# AT32M412_EVB_V0_3.net
KiCad netlist of a schematic drawn in EasyEDA Pro
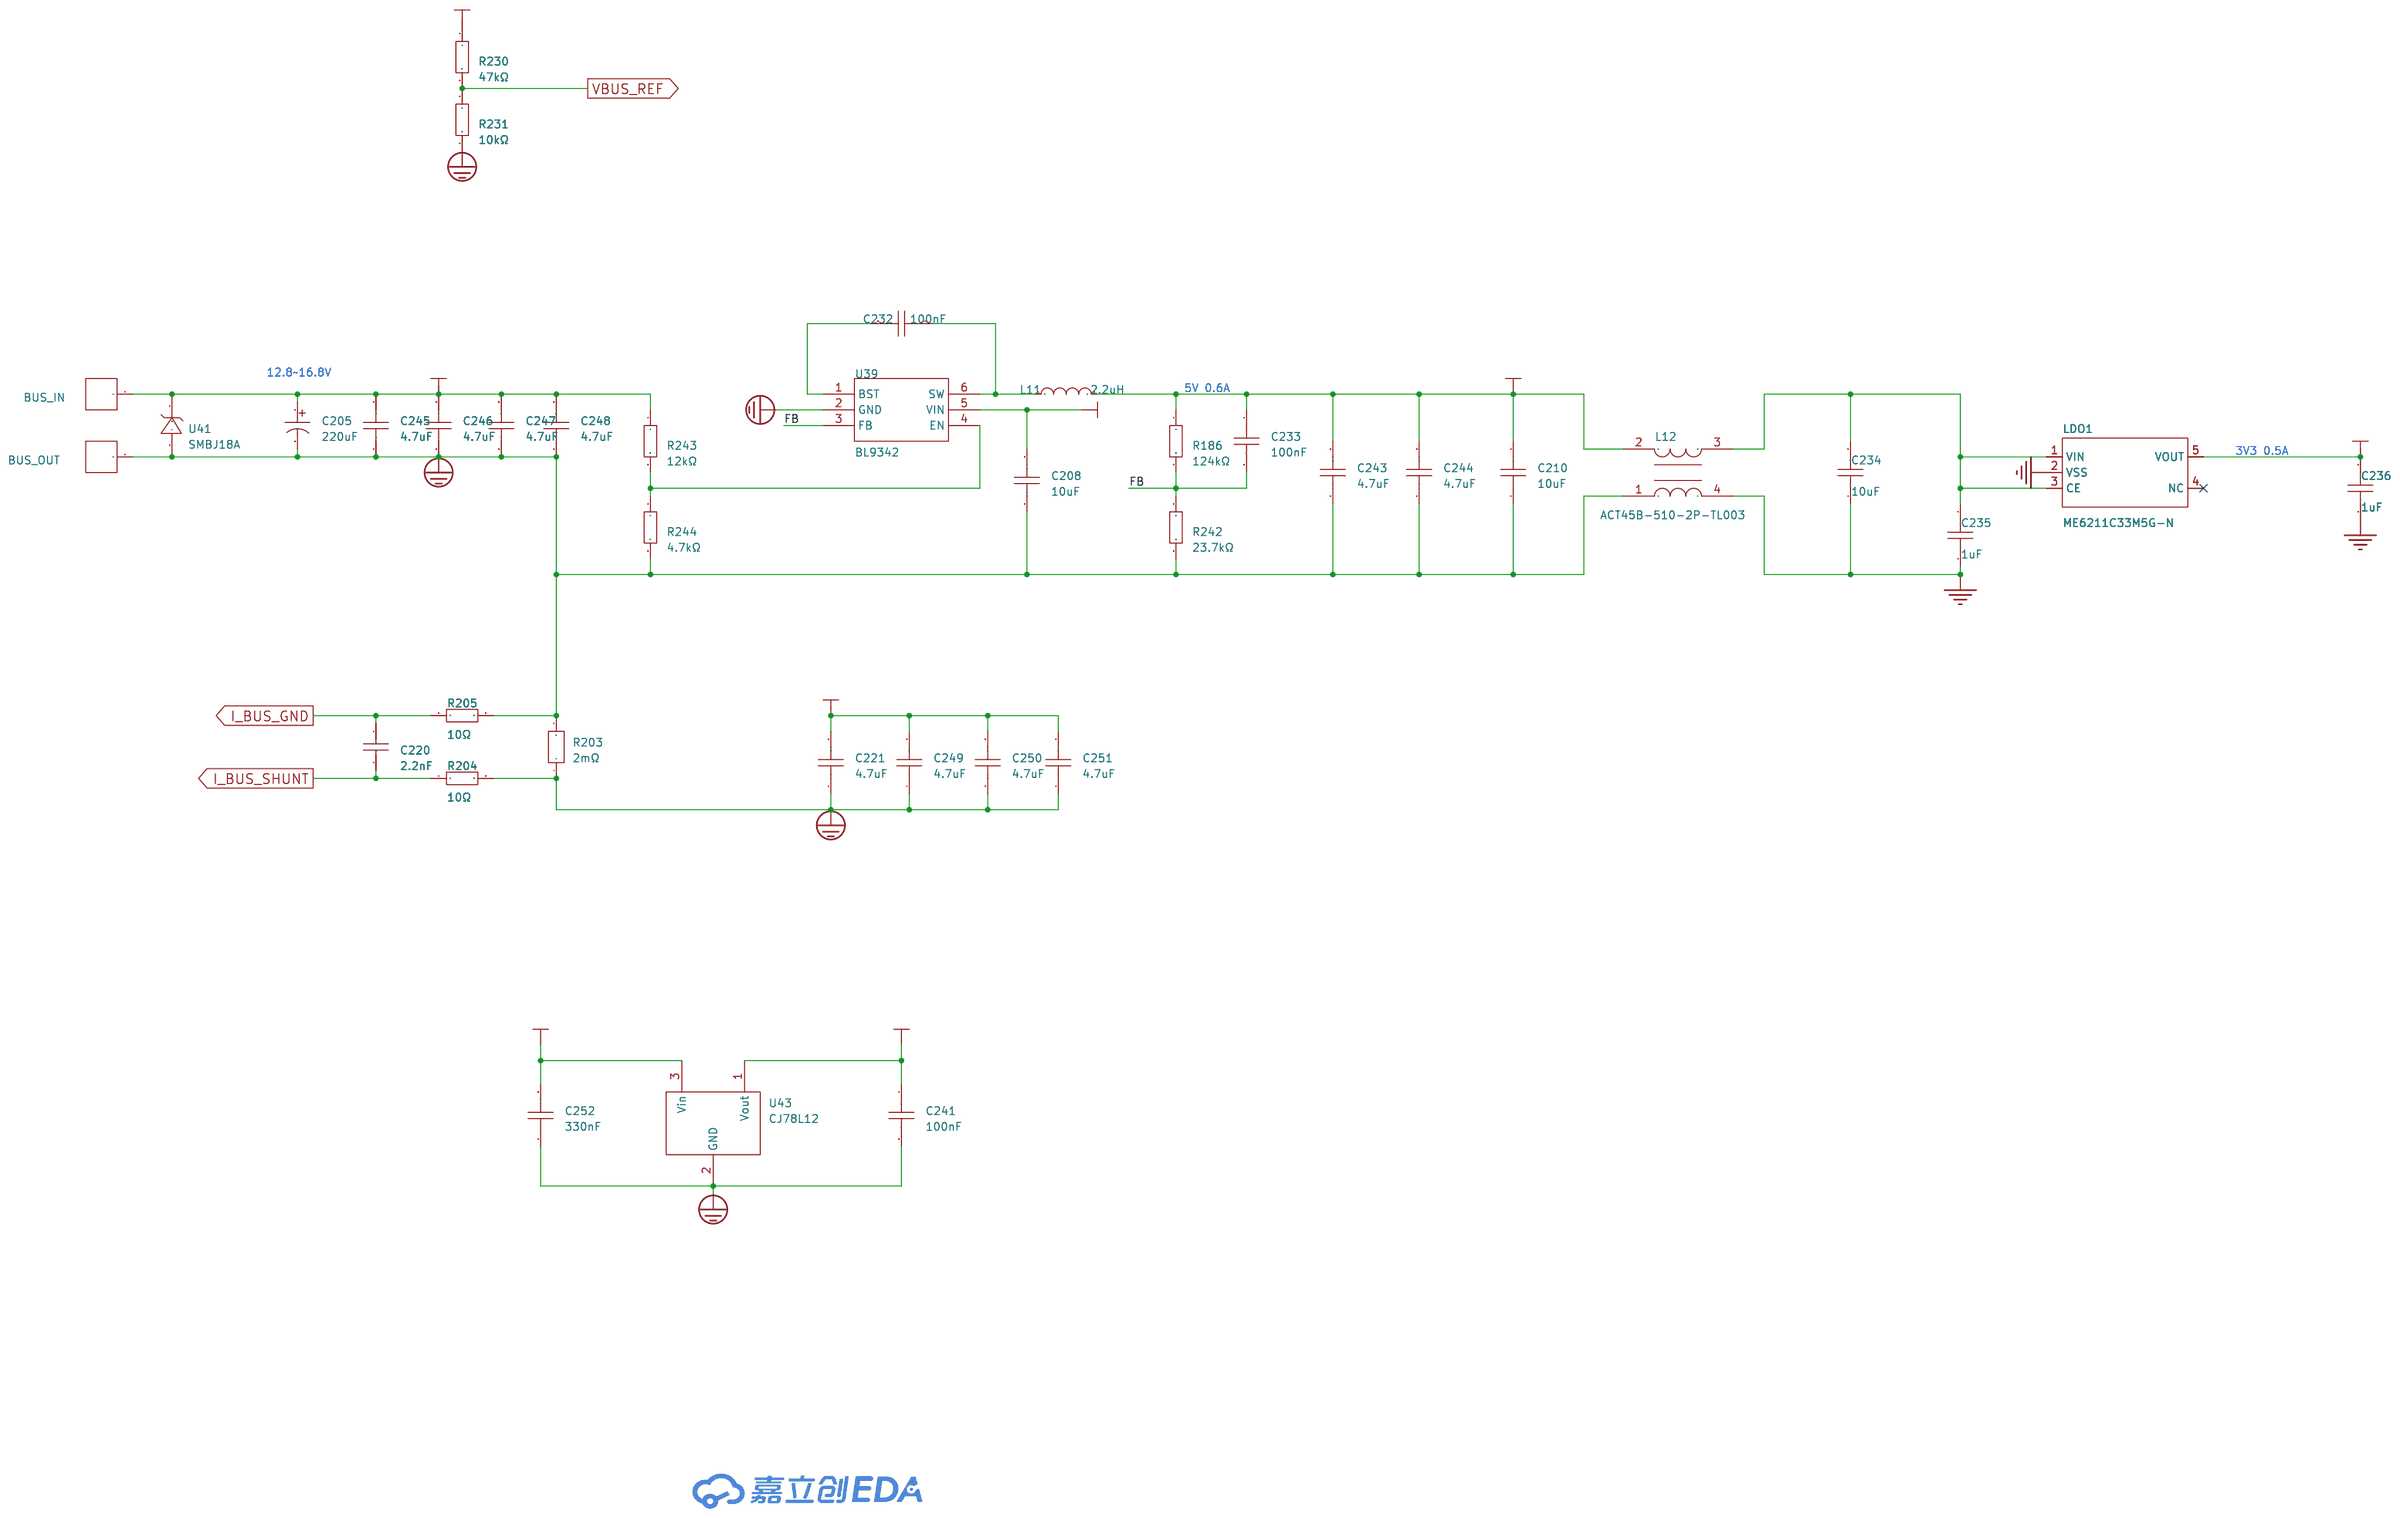
[diagram p0: PWR]
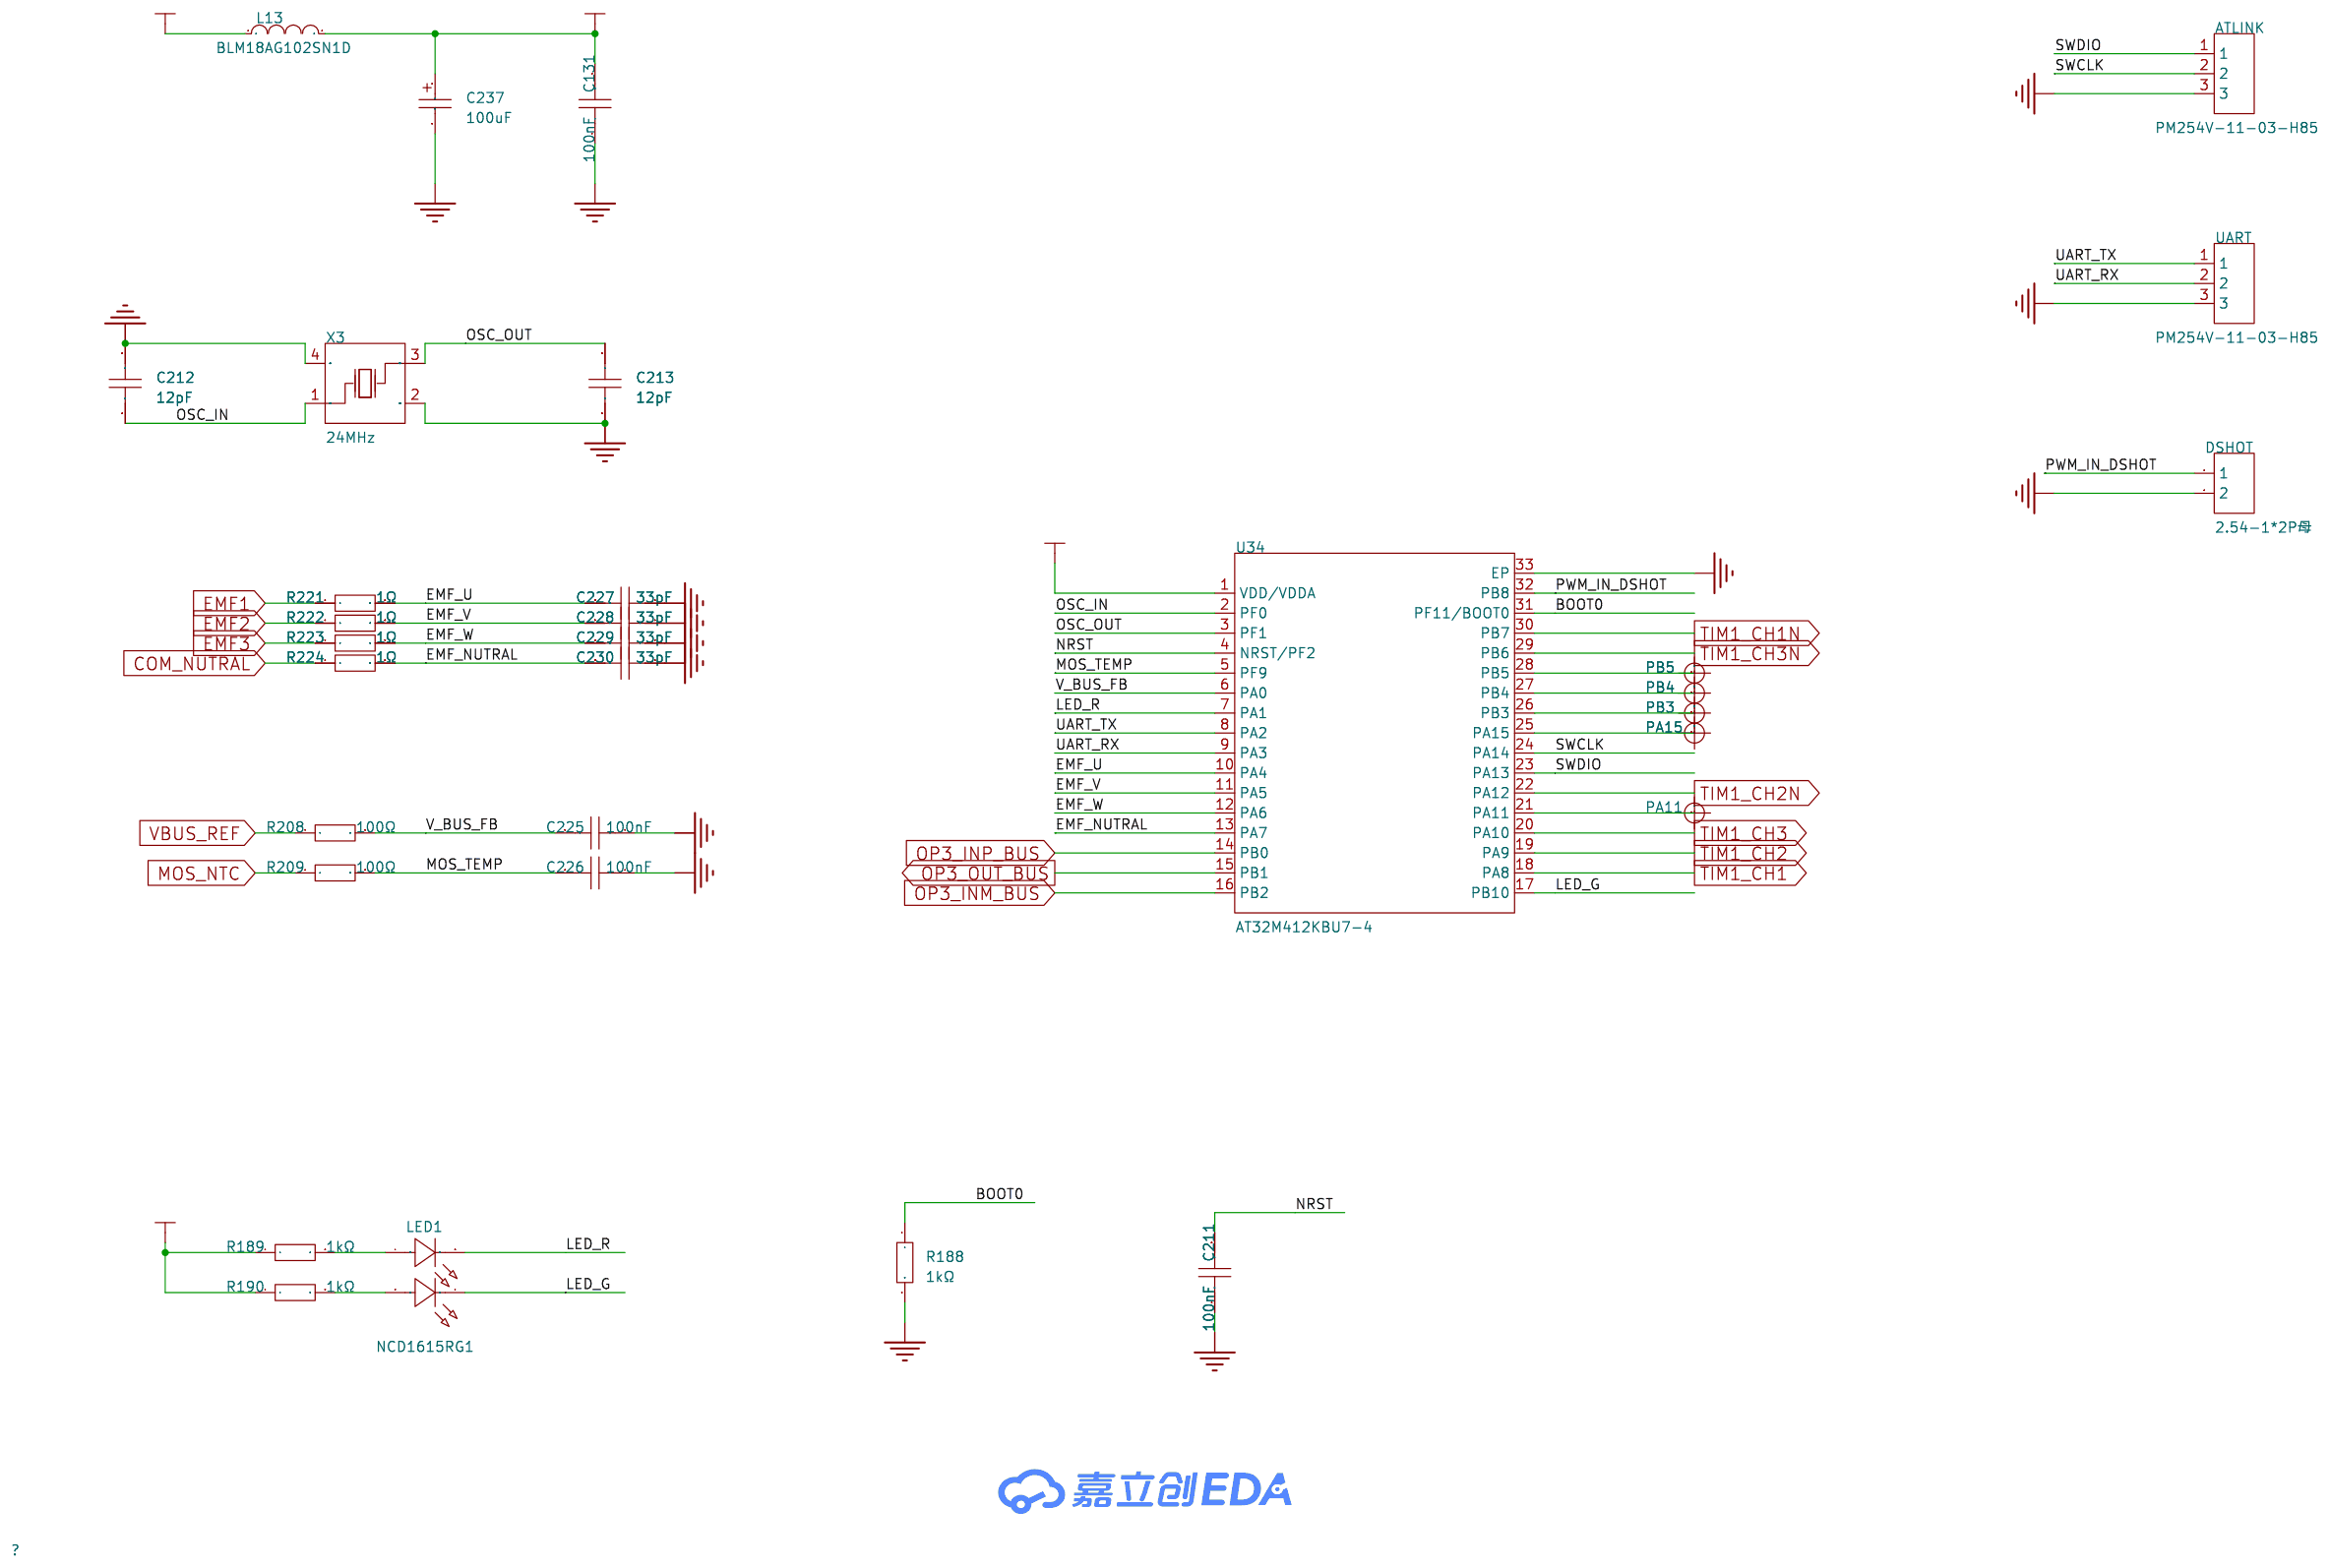
[diagram p1: MCU]
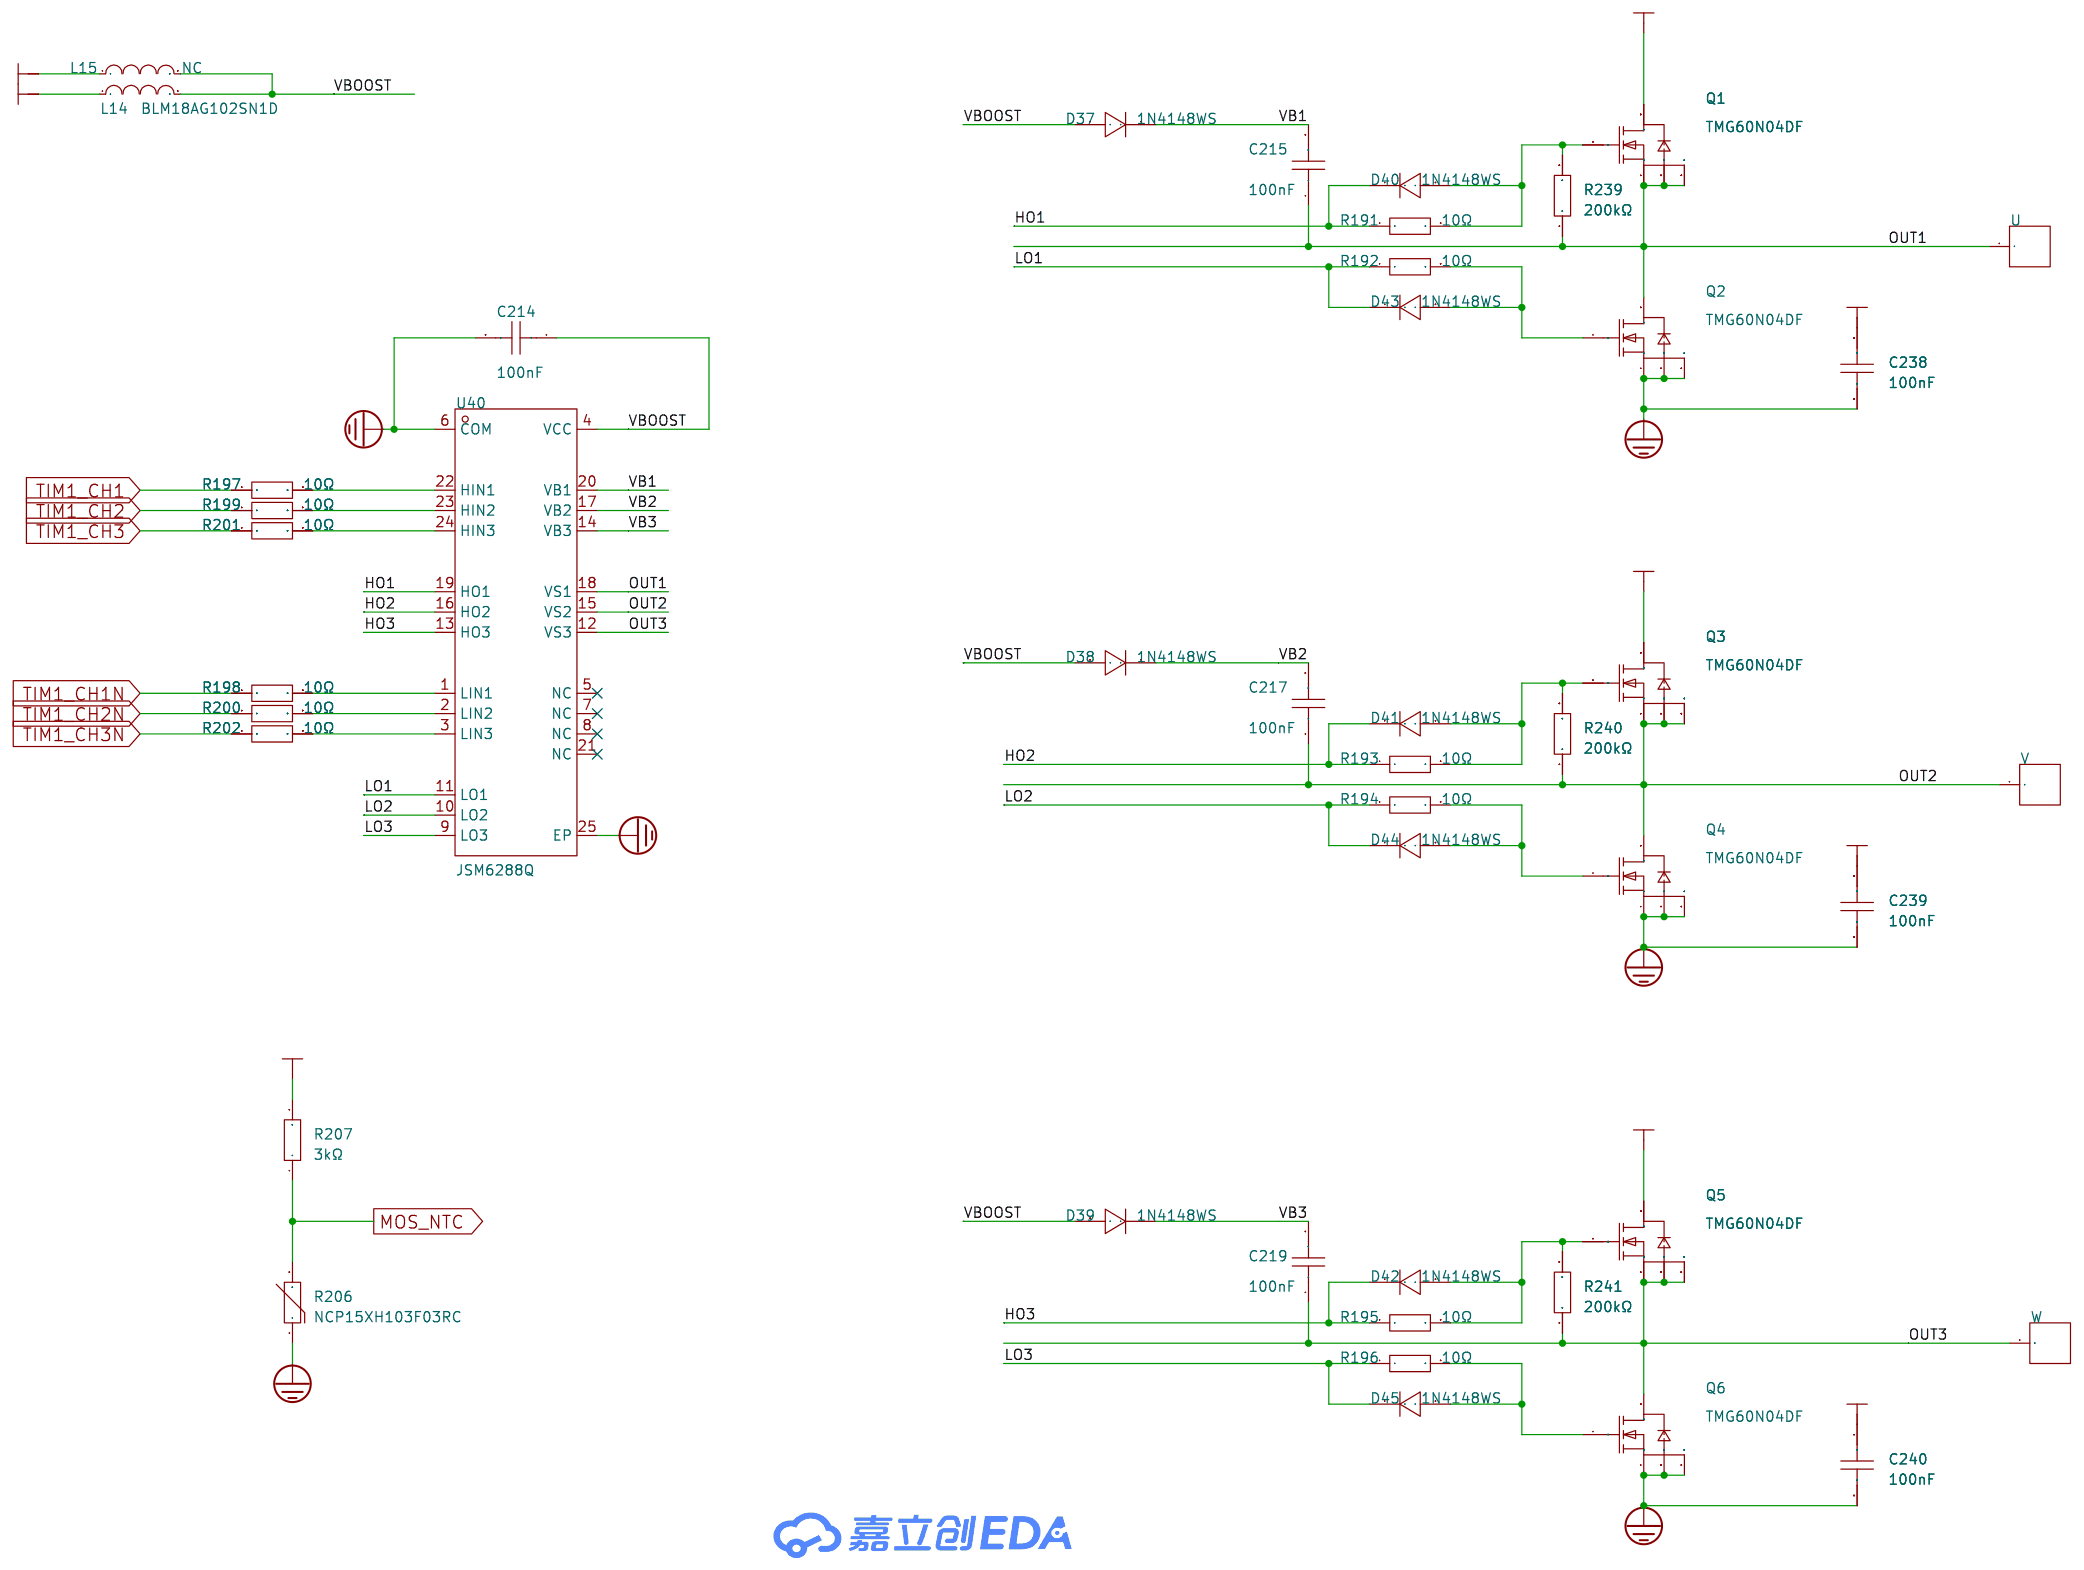
[diagram p2: Driver]
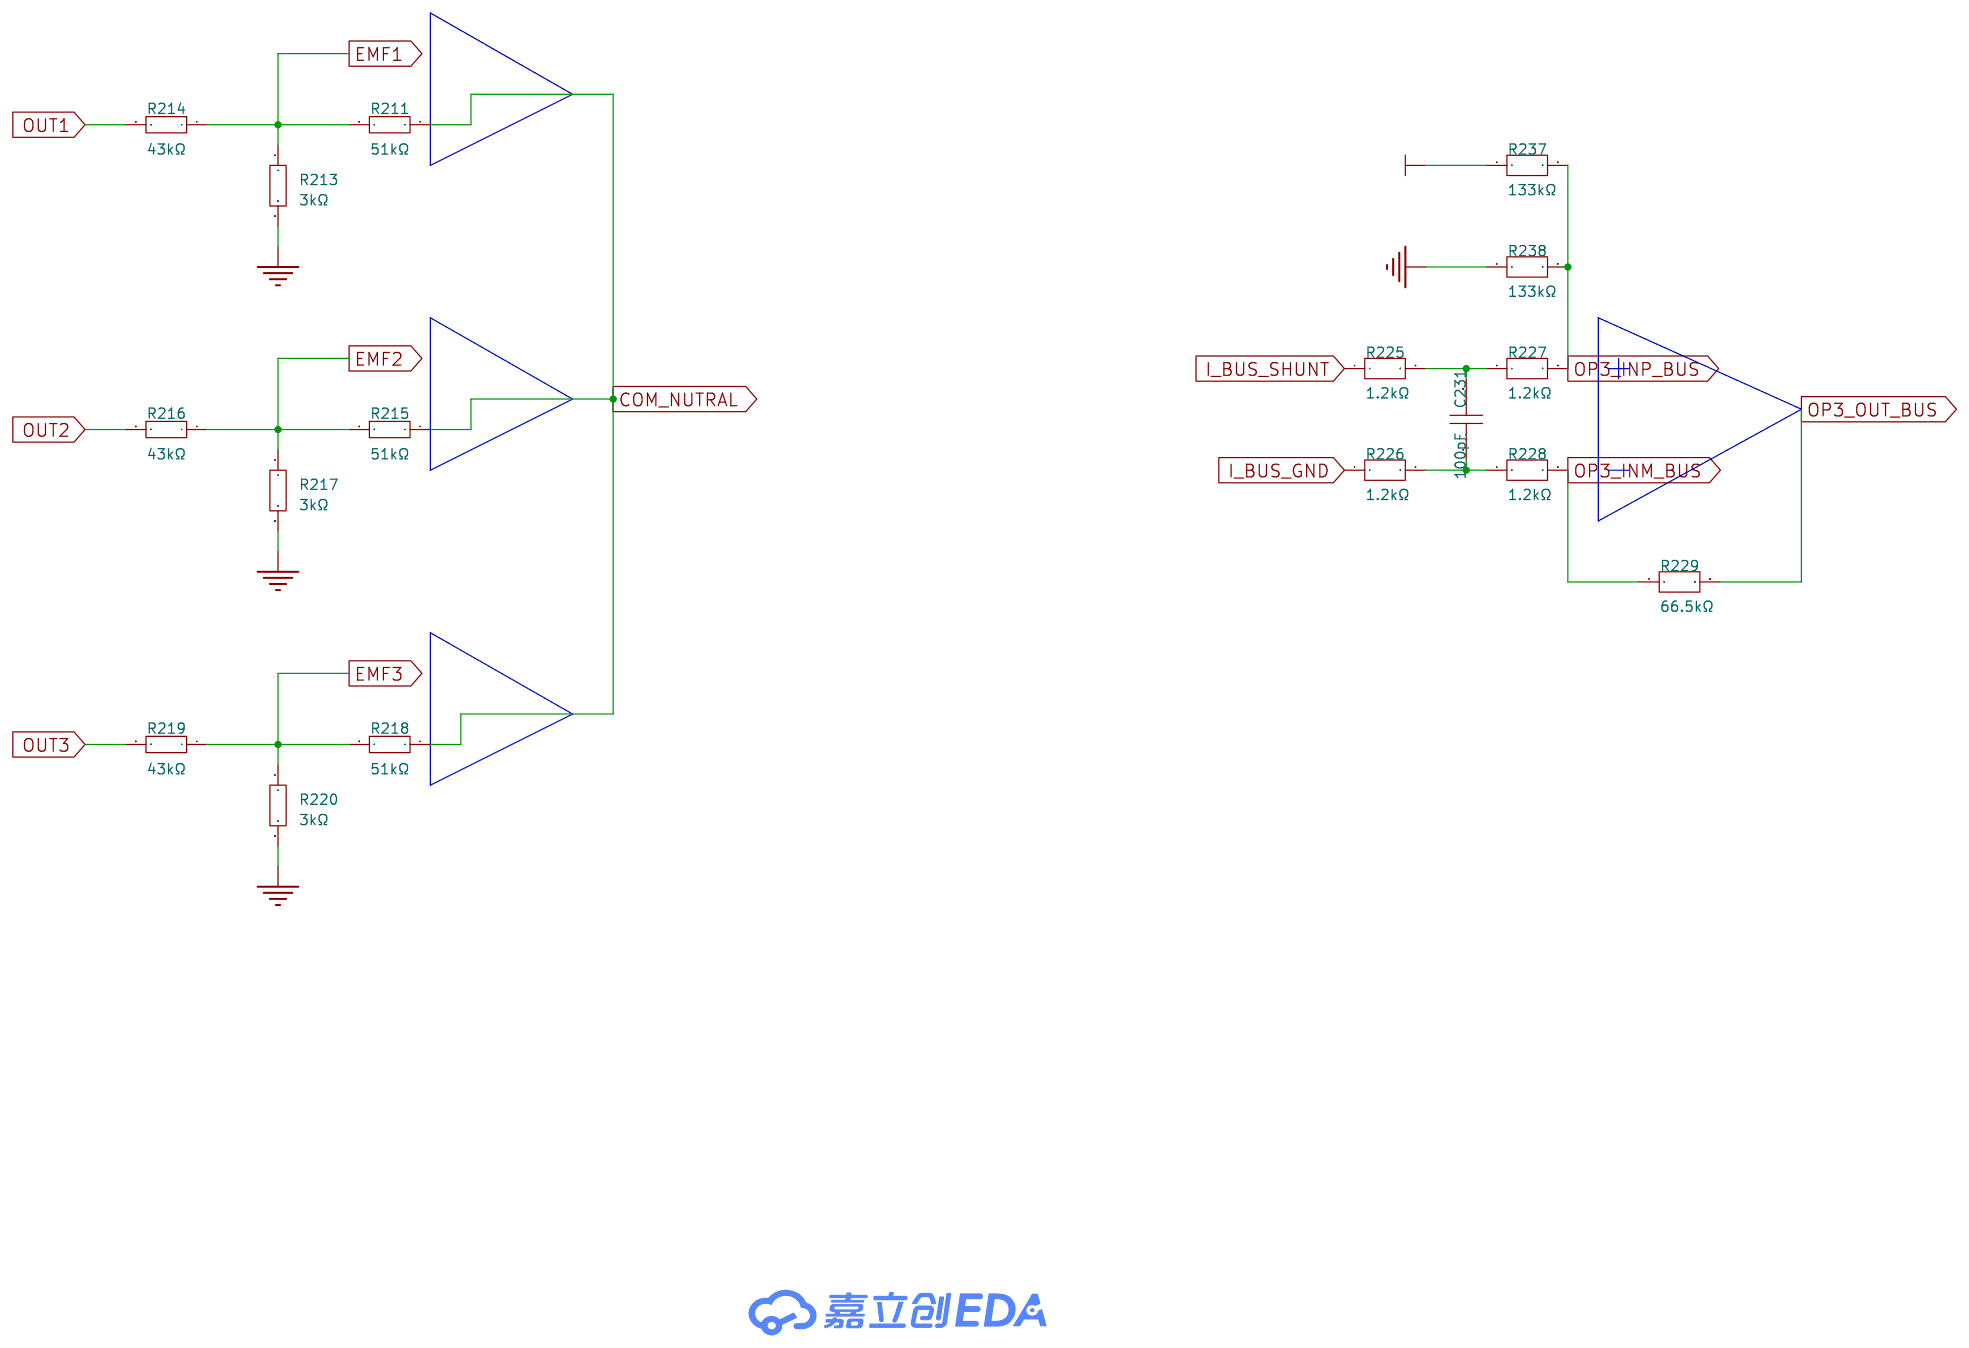
[diagram p3: Sensing]

(export (version "E")
  (design (tool "Eeschema 10.0.6"))
  (components
    (comp (ref "BUS_IN")
      (value "~")
      (footprint "easyedapro:PAD_35A")
      (description "焊盘")
      (libsource (lib "easyedapro") (part "PAD_35A"))
    )
    (comp (ref "BUS_OUT")
      (value "~")
      (footprint "easyedapro:PAD_35A")
      (description "焊盘")
      (libsource (lib "easyedapro") (part "PAD_35A"))
    )
    (comp (ref "C205")
      (value "220uF")
      (footprint "easyedapro:CAP-TH_BD8.0-P3.50-D0.6-FD")
      (description "容值:220uF;精度:±20%;额定电压:35V;")
      (fields (field (name "Manufacturer Part") "ERS1VM221F12OT") (field (name "Manufacturer") "AISHI(艾华集团)"))
      (libsource (lib "easyedapro") (part "ERS1VM221F12OT"))
    )
    (comp (ref "C208")
      (value "10uF")
      (footprint "easyedapro:C0805")
      (description "容值:10uF;精度:±10%;额定电压:25V;温度系数:X5R;")
      (fields
        (field (name "Manufacturer Part") "CL21A106KAYNNNE")
        (field (name "Manufacturer") "SAMSUNG(三星)")
      )
      (libsource (lib "easyedapro") (part "CL21A106KAYNNNE"))
    )
    (comp (ref "C210")
      (value "10uF")
      (footprint "easyedapro:C0402")
      (description "容值:10uF;精度:±20%;额定电压:6.3V;温度系数:X5R;")
      (fields
        (field (name "Manufacturer Part") "CL05A106MQ5NUNC")
        (field (name "Manufacturer") "SAMSUNG(三星)")
      )
      (libsource (lib "easyedapro") (part "GRM155R60J226ME11D"))
    )
    (comp (ref "C220")
      (value "2.2nF")
      (footprint "easyedapro:C0402")
      (description "容值:2.2nF;精度:±10%;额定电压:50V;温度系数:X7R;")
      (fields (field (name "Manufacturer Part") "0402B222K500NT") (field (name "Manufacturer") "FH(风华)"))
      (libsource (lib "easyedapro") (part "0402B222K500NT"))
    )
    (comp (ref "C221")
      (value "4.7uF")
      (footprint "easyedapro:C1210")
      (description "容值:4.7uF;精度:±10%;额定电压:100V;温度系数:X7R;")
      (fields (field (name "Manufacturer Part") "FS32X475K101EGG") (field (name "Manufacturer") "PSA(信昌电陶)"))
      (libsource (lib "easyedapro") (part "FS32X475K101EGG"))
    )
    (comp (ref "C232")
      (value "100nF")
      (footprint "easyedapro:C0402")
      (fields
        (field (name "Manufacturer Part") "CL05B104KO5NNNC")
        (field (name "Manufacturer") "SAMSUNG(三星)")
      )
      (libsource (lib "easyedapro") (part "CapAcitance"))
    )
    (comp (ref "C233")
      (value "100nF")
      (footprint "easyedapro:C0402")
      (fields
        (field (name "Manufacturer Part") "CL05B104KO5NNNC")
        (field (name "Manufacturer") "SAMSUNG(三星)")
      )
      (libsource (lib "easyedapro") (part "CapAcitance"))
    )
    (comp (ref "C234")
      (value "10uF")
      (footprint "easyedapro:C0402")
      (description "容值:10uF;精度:±20%;额定电压:6.3V;温度系数:X5R;")
      (fields
        (field (name "Manufacturer Part") "CL05A106MQ5NUNC")
        (field (name "Manufacturer") "SAMSUNG(三星)")
      )
      (libsource (lib "easyedapro") (part "GRM155R60J226ME11D"))
    )
    (comp (ref "C235")
      (value "1uF")
      (footprint "easyedapro:C0402")
      (description "容值:1uF;精度:±10%;额定电压:25V;温度系数:X5R;")
      (fields
        (field (name "Manufacturer Part") "CL05A105KA5NQNC")
        (field (name "Manufacturer") "SAMSUNG(三星)")
      )
      (libsource (lib "easyedapro") (part "GRM155R60J226ME11D"))
    )
    (comp (ref "C236")
      (value "1uF")
      (footprint "easyedapro:C0402")
      (description "容值:1uF;精度:±10%;额定电压:25V;温度系数:X5R;")
      (fields
        (field (name "Manufacturer Part") "CL05A105KA5NQNC")
        (field (name "Manufacturer") "SAMSUNG(三星)")
      )
      (libsource (lib "easyedapro") (part "GRM155R60J226ME11D"))
    )
    (comp (ref "C241")
      (value "100nF")
      (footprint "easyedapro:C0402")
      (fields
        (field (name "Manufacturer Part") "CL05B104KO5NNNC")
        (field (name "Manufacturer") "SAMSUNG(三星)")
      )
      (libsource (lib "easyedapro") (part "CapAcitance"))
    )
    (comp (ref "C243")
      (value "4.7uF")
      (footprint "easyedapro:C0805")
      (description "容值:4.7uF;精度:±10%;额定电压:50V;温度系数:X7R;")
      (fields (field (name "Manufacturer Part") "0805B475K500NT") (field (name "Manufacturer") "FH(风华)"))
      (libsource (lib "easyedapro") (part "0805B475K500NT"))
    )
    (comp (ref "C244")
      (value "4.7uF")
      (footprint "easyedapro:C0805")
      (description "容值:4.7uF;精度:±10%;额定电压:50V;温度系数:X7R;")
      (fields (field (name "Manufacturer Part") "0805B475K500NT") (field (name "Manufacturer") "FH(风华)"))
      (libsource (lib "easyedapro") (part "0805B475K500NT"))
    )
    (comp (ref "C245")
      (value "4.7uF")
      (footprint "easyedapro:C1210")
      (description "容值:4.7uF;精度:±10%;额定电压:100V;温度系数:X7R;")
      (fields (field (name "Manufacturer Part") "FS32X475K101EGG") (field (name "Manufacturer") "PSA(信昌电陶)"))
      (libsource (lib "easyedapro") (part "FS32X475K101EGG"))
    )
    (comp (ref "C246")
      (value "4.7uF")
      (footprint "easyedapro:C1210")
      (description "容值:4.7uF;精度:±10%;额定电压:100V;温度系数:X7R;")
      (fields (field (name "Manufacturer Part") "FS32X475K101EGG") (field (name "Manufacturer") "PSA(信昌电陶)"))
      (libsource (lib "easyedapro") (part "FS32X475K101EGG"))
    )
    (comp (ref "C247")
      (value "4.7uF")
      (footprint "easyedapro:C1210")
      (description "容值:4.7uF;精度:±10%;额定电压:100V;温度系数:X7R;")
      (fields (field (name "Manufacturer Part") "FS32X475K101EGG") (field (name "Manufacturer") "PSA(信昌电陶)"))
      (libsource (lib "easyedapro") (part "FS32X475K101EGG"))
    )
    (comp (ref "C248")
      (value "4.7uF")
      (footprint "easyedapro:C1210")
      (description "容值:4.7uF;精度:±10%;额定电压:100V;温度系数:X7R;")
      (fields (field (name "Manufacturer Part") "FS32X475K101EGG") (field (name "Manufacturer") "PSA(信昌电陶)"))
      (libsource (lib "easyedapro") (part "FS32X475K101EGG"))
    )
    (comp (ref "C249")
      (value "4.7uF")
      (footprint "easyedapro:C1210")
      (description "容值:4.7uF;精度:±10%;额定电压:100V;温度系数:X7R;")
      (fields (field (name "Manufacturer Part") "FS32X475K101EGG") (field (name "Manufacturer") "PSA(信昌电陶)"))
      (libsource (lib "easyedapro") (part "FS32X475K101EGG"))
    )
    (comp (ref "C250")
      (value "4.7uF")
      (footprint "easyedapro:C1210")
      (description "容值:4.7uF;精度:±10%;额定电压:100V;温度系数:X7R;")
      (fields (field (name "Manufacturer Part") "FS32X475K101EGG") (field (name "Manufacturer") "PSA(信昌电陶)"))
      (libsource (lib "easyedapro") (part "FS32X475K101EGG"))
    )
    (comp (ref "C251")
      (value "4.7uF")
      (footprint "easyedapro:C1210")
      (description "容值:4.7uF;精度:±10%;额定电压:100V;温度系数:X7R;")
      (fields (field (name "Manufacturer Part") "FS32X475K101EGG") (field (name "Manufacturer") "PSA(信昌电陶)"))
      (libsource (lib "easyedapro") (part "FS32X475K101EGG"))
    )
    (comp (ref "C252")
      (value "330nF")
      (footprint "easyedapro:C0805")
      (description "容值:330nF;精度:±10%;额定电压:100V;温度系数:X7R;")
      (fields
        (field (name "Manufacturer Part") "CC0805KKX7R0BB334")
        (field (name "Manufacturer") "YAGEO(国巨)")
      )
      (libsource (lib "easyedapro") (part "CC0805KKX7R0BB334"))
    )
    (comp (ref "L11")
      (value "2.2uH")
      (footprint "easyedapro:IND-SMD_L2.5-W2.0_MHCHL2520")
      (description "电感值:2.2uH;精度:±20%;额定电流:3A;饱和电流(Isat):3.8A;类型:一体成型电感;")
      (fields
        (field (name "Manufacturer Part") "FTC252012S2R2MBCA")
        (field (name "Manufacturer") "cjiang(长江微电)")
      )
      (libsource (lib "easyedapro") (part "FTC252012S2R2MBCA"))
    )
    (comp (ref "L12")
      (value "ACT45B-510-2P-TL003")
      (footprint "easyedapro:IND-SMD_4P-L4.5-W3.2-TL")
      (description "线路数:2;电感 @ 频率:51uH@100kHz;阻抗 @ 频率:2.8kΩ@10MHz;直流电阻(DCR):1Ω;")
      (fields (field (name "Manufacturer") "TDK"))
      (libsource (lib "easyedapro") (part "ACT45B-510-2P-TL003"))
    )
    (comp (ref "LDO1")
      (value "ME6211C33M5G-N")
      (footprint "easyedapro:SOT-23-5_L3.0-W1.7-P0.95-LS2.8-BL")
      (description "输出类型:固定;工作电压:6V;输出电压:3.3V;输出电流:500mA;电源纹波抑制比(PSRR):70dB@(1kHz)；62dB@(10kHz);输出极性:正极;")
      (fields (field (name "Manufacturer") "MICRONE(南京微盟)"))
      (libsource (lib "easyedapro") (part "ME6211C33M5G-N"))
    )
    (comp (ref "R186")
      (value "124kΩ")
      (footprint "easyedapro:R0402")
      (fields
        (field (name "Manufacturer Part") "0402WGF1243TCE")
        (field (name "Manufacturer") "UNI-ROYAL(厚声)")
      )
      (libsource (lib "easyedapro") (part "电阻"))
    )
    (comp (ref "R203")
      (value "2mΩ")
      (footprint "easyedapro:RES-SMD_L6.4-W3.2-1")
      (description "电阻类型:采样电阻;阻值:2mΩ;精度:±1%;额定压降:-;功率:3W;温度系数:±50ppm/°C;安装方式:贴片;")
      (fields
        (field (name "Manufacturer Part") "HoLLR2512-3W-2mR-1%")
        (field (name "Manufacturer") "Milliohm(毫欧)")
      )
      (libsource (lib "easyedapro") (part "HOLLR2512-3W-2MR-1%"))
    )
    (comp (ref "R204")
      (value "10Ω")
      (footprint "easyedapro:R0402")
      (description "电阻类型:厚膜电阻;阻值:10Ω;精度:±1%;功率:62.5mW;工作电压:50V;温度系数:±200ppm/℃;")
      (fields
        (field (name "Manufacturer Part") "0402WGF100JTCE")
        (field (name "Manufacturer") "UNI-ROYAL(厚声)")
      )
      (libsource (lib "easyedapro") (part "电阻"))
    )
    (comp (ref "R205")
      (value "10Ω")
      (footprint "easyedapro:R0402")
      (description "电阻类型:厚膜电阻;阻值:10Ω;精度:±1%;功率:62.5mW;工作电压:50V;温度系数:±200ppm/℃;")
      (fields
        (field (name "Manufacturer Part") "0402WGF100JTCE")
        (field (name "Manufacturer") "UNI-ROYAL(厚声)")
      )
      (libsource (lib "easyedapro") (part "电阻"))
    )
    (comp (ref "R230")
      (value "47kΩ")
      (footprint "easyedapro:R0402")
      (fields
        (field (name "Manufacturer Part") "0402WGF4702TCE")
        (field (name "Manufacturer") "UNI-ROYAL(厚声)")
      )
      (libsource (lib "easyedapro") (part "电阻"))
    )
    (comp (ref "R231")
      (value "10kΩ")
      (footprint "easyedapro:R0402")
      (description "电阻类型:厚膜电阻;阻值:10kΩ;精度:±1%;功率:62.5mW;工作电压:50V;温度系数:±100ppm/℃;")
      (fields
        (field (name "Manufacturer Part") "0402WGF1002TCE")
        (field (name "Manufacturer") "UNI-ROYAL(厚声)")
      )
      (libsource (lib "easyedapro") (part "电阻"))
    )
    (comp (ref "R242")
      (value "23.7kΩ")
      (footprint "easyedapro:R0402")
      (fields (field (name "Manufacturer Part") "RC0402FR-0723K7L") (field (name "Manufacturer") "YAGEO(国巨)"))
      (libsource (lib "easyedapro") (part "电阻"))
    )
    (comp (ref "R243")
      (value "12kΩ")
      (footprint "easyedapro:R0402")
      (fields
        (field (name "Manufacturer Part") "0402WGF1202TCE")
        (field (name "Manufacturer") "UNI-ROYAL(厚声)")
      )
      (libsource (lib "easyedapro") (part "电阻"))
    )
    (comp (ref "R244")
      (value "4.7kΩ")
      (footprint "easyedapro:R0402")
      (description "电阻类型:厚膜电阻;阻值:4.7kΩ;精度:±1%;功率:62.5mW;工作电压:50V;温度系数:±100ppm/℃;")
      (fields
        (field (name "Manufacturer Part") "0402WGF4701TCE")
        (field (name "Manufacturer") "UNI-ROYAL(厚声)")
      )
      (libsource (lib "easyedapro") (part "电阻"))
    )
    (comp (ref "U39")
      (value "BL9342")
      (footprint "easyedapro:SOT-23-6_L2.9-W1.6-P0.95-LS2.8-BL")
      (description "功能类型:降压型;工作电压:4.2V~40V;输出电压:-;输出电流:600mA;输出类型:可调;")
      (fields (field (name "Manufacturer") "BL(上海贝岭)"))
      (libsource (lib "easyedapro") (part "BL9342"))
    )
    (comp (ref "U41")
      (value "SMBJ18A")
      (footprint "easyedapro:SMB_L4.5-W3.6-LS5.4-RD")
      (fields (field (name "Manufacturer") "R+O(宏嘉诚)"))
      (libsource (lib "easyedapro") (part "SMBJ18A_C19077573"))
    )
    (comp (ref "U43")
      (value "CJ78L12")
      (footprint "easyedapro:SOT-89-3_L4.5-W2.5-P1.50-LS4.2-BR")
      (description "输出类型:固定;工作电压:35V;输出电压:12V;输出电流:100mA;电源纹波抑制比(PSRR):42dB@(120Hz);输出极性:正极;")
      (fields (field (name "Manufacturer") "CJ(江苏长电/长晶)"))
      (libsource (lib "easyedapro") (part "CJ78L12_C8615"))
    )
    (comp (ref "ATLINK")
      (value "PM254V-11-03-H85")
      (footprint "easyedapro:HDR-TH_3P-P2.54-V-F")
      (fields (field (name "Manufacturer") "XFCN(兴飞)"))
      (libsource (lib "easyedapro") (part "PM254V-11-03-H85"))
    )
    (comp (ref "C131")
      (value "100nF")
      (footprint "easyedapro:C0402")
      (fields
        (field (name "Manufacturer Part") "CL05B104KO5NNNC")
        (field (name "Manufacturer") "SAMSUNG(三星)")
      )
      (libsource (lib "easyedapro") (part "CapAcitance"))
    )
    (comp (ref "C211")
      (value "100nF")
      (footprint "easyedapro:C0402")
      (fields
        (field (name "Manufacturer Part") "CL05B104KO5NNNC")
        (field (name "Manufacturer") "SAMSUNG(三星)")
      )
      (libsource (lib "easyedapro") (part "CapAcitance"))
    )
    (comp (ref "C212")
      (value "12pF")
      (footprint "easyedapro:C0402")
      (fields (field (name "Manufacturer Part") "0402CG120J500NT") (field (name "Manufacturer") "FH(风华)"))
      (libsource (lib "easyedapro") (part "CapAcitance"))
    )
    (comp (ref "C213")
      (value "12pF")
      (footprint "easyedapro:C0402")
      (fields (field (name "Manufacturer Part") "0402CG120J500NT") (field (name "Manufacturer") "FH(风华)"))
      (libsource (lib "easyedapro") (part "CapAcitance"))
    )
    (comp (ref "C225")
      (value "100nF")
      (footprint "easyedapro:C0402")
      (fields
        (field (name "Manufacturer Part") "CL05B104KO5NNNC")
        (field (name "Manufacturer") "SAMSUNG(三星)")
      )
      (libsource (lib "easyedapro") (part "CapAcitance"))
    )
    (comp (ref "C226")
      (value "100nF")
      (footprint "easyedapro:C0402")
      (fields
        (field (name "Manufacturer Part") "CL05B104KO5NNNC")
        (field (name "Manufacturer") "SAMSUNG(三星)")
      )
      (libsource (lib "easyedapro") (part "CapAcitance"))
    )
    (comp (ref "C227")
      (value "33pF")
      (footprint "easyedapro:C0402")
      (fields (field (name "Manufacturer Part") "0402CG330J500NT") (field (name "Manufacturer") "FH(风华)"))
      (libsource (lib "easyedapro") (part "CapAcitance"))
    )
    (comp (ref "C228")
      (value "33pF")
      (footprint "easyedapro:C0402")
      (fields (field (name "Manufacturer Part") "0402CG330J500NT") (field (name "Manufacturer") "FH(风华)"))
      (libsource (lib "easyedapro") (part "CapAcitance"))
    )
    (comp (ref "C229")
      (value "33pF")
      (footprint "easyedapro:C0402")
      (fields (field (name "Manufacturer Part") "0402CG330J500NT") (field (name "Manufacturer") "FH(风华)"))
      (libsource (lib "easyedapro") (part "CapAcitance"))
    )
    (comp (ref "C230")
      (value "33pF")
      (footprint "easyedapro:C0402")
      (fields (field (name "Manufacturer Part") "0402CG330J500NT") (field (name "Manufacturer") "FH(风华)"))
      (libsource (lib "easyedapro") (part "CapAcitance"))
    )
    (comp (ref "C237")
      (value "100uF")
      (footprint "easyedapro:CASE-B_3528")
      (description "容值:100uF;精度:±10%;额定电压:6.3V;等效串联电阻:1.7Ω@100kHz;")
      (fields (field (name "Manufacturer Part") "TAJB107K006RNJ") (field (name "Manufacturer") "Kyocera AVX"))
      (libsource (lib "easyedapro") (part "TAJB107K006RNJ"))
    )
    (comp (ref "DSHOT")
      (value "2.54-1*2P母")
      (footprint "easyedapro:HDR-TH_2P-P2.54-V-F")
      (fields (field (name "Manufacturer") "BOOMELE(博穆精密)"))
      (libsource (lib "easyedapro") (part "Header-Female-2.54_1x2"))
    )
    (comp (ref "L13")
      (value "BLM18AG102SN1D")
      (footprint "easyedapro:L0603")
      (description "标称阻抗@测试频率:1kΩ@100MHz;误差:±25%;直流电阻(RDC):500mΩ;")
      (fields (field (name "Manufacturer") "muRata(村田)"))
      (libsource (lib "easyedapro") (part "BLM18AG102SN1D"))
    )
    (comp (ref "LED1")
      (value "NCD1615RG1")
      (footprint "easyedapro:LED-SMD_4P-L1.6-W1.5-TL-1")
      (fields (field (name "Manufacturer") "国星光电"))
      (libsource (lib "easyedapro") (part "NCD1615RG1"))
    )
    (comp (ref "PA11")
      (value "~")
      (footprint "easyedapro:Mark-Point-1mm")
      (description "Mark点")
      (libsource (lib "easyedapro") (part "Mark-Point"))
    )
    (comp (ref "PA15")
      (value "~")
      (footprint "easyedapro:Mark-Point-1mm")
      (description "Mark点")
      (libsource (lib "easyedapro") (part "Mark-Point"))
    )
    (comp (ref "PB3")
      (value "~")
      (footprint "easyedapro:Mark-Point-1mm")
      (description "Mark点")
      (libsource (lib "easyedapro") (part "Mark-Point"))
    )
    (comp (ref "PB4")
      (value "~")
      (footprint "easyedapro:Mark-Point-1mm")
      (description "Mark点")
      (libsource (lib "easyedapro") (part "Mark-Point"))
    )
    (comp (ref "PB5")
      (value "~")
      (footprint "easyedapro:Mark-Point-1mm")
      (description "Mark点")
      (libsource (lib "easyedapro") (part "Mark-Point"))
    )
    (comp (ref "R188")
      (value "1kΩ")
      (footprint "easyedapro:R0402")
      (description "电阻类型:厚膜电阻;阻值:1kΩ;精度:±1%;功率:62.5mW;工作电压:50V;温度系数:±100ppm/℃;")
      (fields
        (field (name "Manufacturer Part") "0402WGF1001TCE")
        (field (name "Manufacturer") "UNI-ROYAL(厚声)")
      )
      (libsource (lib "easyedapro") (part "电阻"))
    )
    (comp (ref "R189")
      (value "1kΩ")
      (footprint "easyedapro:R0402")
      (description "电阻类型:厚膜电阻;阻值:1kΩ;精度:±1%;功率:62.5mW;工作电压:50V;温度系数:±100ppm/℃;")
      (fields
        (field (name "Manufacturer Part") "0402WGF1001TCE")
        (field (name "Manufacturer") "UNI-ROYAL(厚声)")
      )
      (libsource (lib "easyedapro") (part "电阻"))
    )
    (comp (ref "R190")
      (value "1kΩ")
      (footprint "easyedapro:R0402")
      (description "电阻类型:厚膜电阻;阻值:1kΩ;精度:±1%;功率:62.5mW;工作电压:50V;温度系数:±100ppm/℃;")
      (fields
        (field (name "Manufacturer Part") "0402WGF1001TCE")
        (field (name "Manufacturer") "UNI-ROYAL(厚声)")
      )
      (libsource (lib "easyedapro") (part "电阻"))
    )
    (comp (ref "R208")
      (value "100Ω")
      (footprint "easyedapro:R0402")
      (fields
        (field (name "Manufacturer Part") "0402WGF1000TCE")
        (field (name "Manufacturer") "UNI-ROYAL(厚声)")
      )
      (libsource (lib "easyedapro") (part "电阻"))
    )
    (comp (ref "R209")
      (value "100Ω")
      (footprint "easyedapro:R0402")
      (fields
        (field (name "Manufacturer Part") "0402WGF1000TCE")
        (field (name "Manufacturer") "UNI-ROYAL(厚声)")
      )
      (libsource (lib "easyedapro") (part "电阻"))
    )
    (comp (ref "R221")
      (value "1Ω")
      (footprint "easyedapro:R0402")
      (fields
        (field (name "Manufacturer Part") "0402WGF100KTCE")
        (field (name "Manufacturer") "UNI-ROYAL(厚声)")
      )
      (libsource (lib "easyedapro") (part "电阻"))
    )
    (comp (ref "R222")
      (value "1Ω")
      (footprint "easyedapro:R0402")
      (fields
        (field (name "Manufacturer Part") "0402WGF100KTCE")
        (field (name "Manufacturer") "UNI-ROYAL(厚声)")
      )
      (libsource (lib "easyedapro") (part "电阻"))
    )
    (comp (ref "R223")
      (value "1Ω")
      (footprint "easyedapro:R0402")
      (fields
        (field (name "Manufacturer Part") "0402WGF100KTCE")
        (field (name "Manufacturer") "UNI-ROYAL(厚声)")
      )
      (libsource (lib "easyedapro") (part "电阻"))
    )
    (comp (ref "R224")
      (value "1Ω")
      (footprint "easyedapro:R0402")
      (fields
        (field (name "Manufacturer Part") "0402WGF100KTCE")
        (field (name "Manufacturer") "UNI-ROYAL(厚声)")
      )
      (libsource (lib "easyedapro") (part "电阻"))
    )
    (comp (ref "U34")
      (value "AT32M412KBU7-4")
      (footprint "easyedapro:WQFN-32_L4.0-W4.0-P0.40-TL-EP2.7")
      (fields (field (name "Manufacturer") "ARTERY(雅特力)"))
      (libsource (lib "easyedapro") (part "AT32M412KBU7-4"))
    )
    (comp (ref "UART")
      (value "PM254V-11-03-H85")
      (footprint "easyedapro:HDR-TH_3P-P2.54-V-F")
      (fields (field (name "Manufacturer") "XFCN(兴飞)"))
      (libsource (lib "easyedapro") (part "PM254V-11-03-H85"))
    )
    (comp (ref "X3")
      (value "24MHz")
      (footprint "easyedapro:CRYSTAL-SMD_4P-L3.2-W2.5-BL")
      (description "晶振类型:贴片晶振;频率:24MHz;常温频差:±10ppm;负载电容:12pF;频率稳定度:±20ppm;")
      (fields (field (name "Manufacturer Part") "X322524MOB4SI") (field (name "Manufacturer") "YXC(扬兴晶振)"))
      (libsource (lib "easyedapro") (part "X322524MOB4SI"))
    )
    (comp (ref "C214")
      (value "100nF")
      (footprint "easyedapro:C0402")
      (description "容值:100nF;精度:±10%;额定电压:50V;温度系数:X7R;")
      (fields
        (field (name "Manufacturer Part") "CL05B104KB54PNC")
        (field (name "Manufacturer") "SAMSUNG(三星)")
      )
      (libsource (lib "easyedapro") (part "CL05B104KB54PNC"))
    )
    (comp (ref "C215")
      (value "100nF")
      (footprint "easyedapro:C0402")
      (description "容值:100nF;精度:±10%;额定电压:50V;温度系数:X7R;")
      (fields
        (field (name "Manufacturer Part") "CL05B104KB54PNC")
        (field (name "Manufacturer") "SAMSUNG(三星)")
      )
      (libsource (lib "easyedapro") (part "CL05B104KB54PNC"))
    )
    (comp (ref "C217")
      (value "100nF")
      (footprint "easyedapro:C0402")
      (description "容值:100nF;精度:±10%;额定电压:50V;温度系数:X7R;")
      (fields
        (field (name "Manufacturer Part") "CL05B104KB54PNC")
        (field (name "Manufacturer") "SAMSUNG(三星)")
      )
      (libsource (lib "easyedapro") (part "CL05B104KB54PNC"))
    )
    (comp (ref "C219")
      (value "100nF")
      (footprint "easyedapro:C0402")
      (description "容值:100nF;精度:±10%;额定电压:50V;温度系数:X7R;")
      (fields
        (field (name "Manufacturer Part") "CL05B104KB54PNC")
        (field (name "Manufacturer") "SAMSUNG(三星)")
      )
      (libsource (lib "easyedapro") (part "CL05B104KB54PNC"))
    )
    (comp (ref "C238")
      (value "100nF")
      (footprint "easyedapro:C0402")
      (description "容值:100nF;精度:±10%;额定电压:50V;温度系数:X7R;")
      (fields
        (field (name "Manufacturer Part") "CL05B104KB54PNC")
        (field (name "Manufacturer") "SAMSUNG(三星)")
      )
      (libsource (lib "easyedapro") (part "CL05B104KB54PNC"))
    )
    (comp (ref "C239")
      (value "100nF")
      (footprint "easyedapro:C0402")
      (description "容值:100nF;精度:±10%;额定电压:50V;温度系数:X7R;")
      (fields
        (field (name "Manufacturer Part") "CL05B104KB54PNC")
        (field (name "Manufacturer") "SAMSUNG(三星)")
      )
      (libsource (lib "easyedapro") (part "CL05B104KB54PNC"))
    )
    (comp (ref "C240")
      (value "100nF")
      (footprint "easyedapro:C0402")
      (description "容值:100nF;精度:±10%;额定电压:50V;温度系数:X7R;")
      (fields
        (field (name "Manufacturer Part") "CL05B104KB54PNC")
        (field (name "Manufacturer") "SAMSUNG(三星)")
      )
      (libsource (lib "easyedapro") (part "CL05B104KB54PNC"))
    )
    (comp (ref "D37")
      (value "1N4148WS")
      (footprint "easyedapro:SOD-323_L1.8-W1.3-LS2.5-RD")
      (description "二极管配置:独立式;正向压降(Vf):1.25V@150mA;直流反向耐压(Vr):100V;整流电流:150mA;反向恢复时间(Trr):4ns;")
      (fields (field (name "Manufacturer") "CJ(江苏长电/长晶)"))
      (libsource (lib "easyedapro") (part "1N4148WS T4"))
    )
    (comp (ref "D38")
      (value "1N4148WS")
      (footprint "easyedapro:SOD-323_L1.8-W1.3-LS2.5-RD")
      (description "二极管配置:独立式;正向压降(Vf):1.25V@150mA;直流反向耐压(Vr):100V;整流电流:150mA;反向恢复时间(Trr):4ns;")
      (fields (field (name "Manufacturer") "CJ(江苏长电/长晶)"))
      (libsource (lib "easyedapro") (part "1N4148WS T4"))
    )
    (comp (ref "D39")
      (value "1N4148WS")
      (footprint "easyedapro:SOD-323_L1.8-W1.3-LS2.5-RD")
      (description "二极管配置:独立式;正向压降(Vf):1.25V@150mA;直流反向耐压(Vr):100V;整流电流:150mA;反向恢复时间(Trr):4ns;")
      (fields (field (name "Manufacturer") "CJ(江苏长电/长晶)"))
      (libsource (lib "easyedapro") (part "1N4148WS T4"))
    )
    (comp (ref "D40")
      (value "1N4148WS")
      (footprint "easyedapro:SOD-323_L1.8-W1.3-LS2.5-RD")
      (description "二极管配置:独立式;正向压降(Vf):1.25V@150mA;直流反向耐压(Vr):100V;整流电流:150mA;反向恢复时间(Trr):4ns;")
      (fields (field (name "Manufacturer") "CJ(江苏长电/长晶)"))
      (libsource (lib "easyedapro") (part "1N4148WS T4"))
    )
    (comp (ref "D41")
      (value "1N4148WS")
      (footprint "easyedapro:SOD-323_L1.8-W1.3-LS2.5-RD")
      (description "二极管配置:独立式;正向压降(Vf):1.25V@150mA;直流反向耐压(Vr):100V;整流电流:150mA;反向恢复时间(Trr):4ns;")
      (fields (field (name "Manufacturer") "CJ(江苏长电/长晶)"))
      (libsource (lib "easyedapro") (part "1N4148WS T4"))
    )
    (comp (ref "D42")
      (value "1N4148WS")
      (footprint "easyedapro:SOD-323_L1.8-W1.3-LS2.5-RD")
      (description "二极管配置:独立式;正向压降(Vf):1.25V@150mA;直流反向耐压(Vr):100V;整流电流:150mA;反向恢复时间(Trr):4ns;")
      (fields (field (name "Manufacturer") "CJ(江苏长电/长晶)"))
      (libsource (lib "easyedapro") (part "1N4148WS T4"))
    )
    (comp (ref "D43")
      (value "1N4148WS")
      (footprint "easyedapro:SOD-323_L1.8-W1.3-LS2.5-RD")
      (description "二极管配置:独立式;正向压降(Vf):1.25V@150mA;直流反向耐压(Vr):100V;整流电流:150mA;反向恢复时间(Trr):4ns;")
      (fields (field (name "Manufacturer") "CJ(江苏长电/长晶)"))
      (libsource (lib "easyedapro") (part "1N4148WS T4"))
    )
    (comp (ref "D44")
      (value "1N4148WS")
      (footprint "easyedapro:SOD-323_L1.8-W1.3-LS2.5-RD")
      (description "二极管配置:独立式;正向压降(Vf):1.25V@150mA;直流反向耐压(Vr):100V;整流电流:150mA;反向恢复时间(Trr):4ns;")
      (fields (field (name "Manufacturer") "CJ(江苏长电/长晶)"))
      (libsource (lib "easyedapro") (part "1N4148WS T4"))
    )
    (comp (ref "D45")
      (value "1N4148WS")
      (footprint "easyedapro:SOD-323_L1.8-W1.3-LS2.5-RD")
      (description "二极管配置:独立式;正向压降(Vf):1.25V@150mA;直流反向耐压(Vr):100V;整流电流:150mA;反向恢复时间(Trr):4ns;")
      (fields (field (name "Manufacturer") "CJ(江苏长电/长晶)"))
      (libsource (lib "easyedapro") (part "1N4148WS T4"))
    )
    (comp (ref "L14")
      (value "BLM18AG102SN1D")
      (footprint "easyedapro:L0603")
      (description "标称阻抗@测试频率:1kΩ@100MHz;误差:±25%;直流电阻(RDC):500mΩ;")
      (fields (field (name "Manufacturer") "muRata(村田)"))
      (libsource (lib "easyedapro") (part "BLM18AG102SN1D"))
    )
    (comp (ref "L15")
      (value "NC")
      (footprint "easyedapro:L0603")
      (description "标称阻抗@测试频率:1kΩ@100MHz;误差:±25%;直流电阻(RDC):500mΩ;")
      (fields (field (name "Manufacturer") "muRata(村田)"))
      (libsource (lib "easyedapro") (part "BLM18AG102SN1D"))
    )
    (comp (ref "Q1")
      (value "TMG60N04DF")
      (footprint "easyedapro:POWERDI3333-8_DMN7022LFGQ-7")
      (fields (field (name "Manufacturer") "TMC(台懋)"))
      (libsource (lib "easyedapro") (part "TMG60N04DF"))
    )
    (comp (ref "Q2")
      (value "TMG60N04DF")
      (footprint "easyedapro:POWERDI3333-8_DMN7022LFGQ-7")
      (fields (field (name "Manufacturer") "TMC(台懋)"))
      (libsource (lib "easyedapro") (part "TMG60N04DF"))
    )
    (comp (ref "Q3")
      (value "TMG60N04DF")
      (footprint "easyedapro:POWERDI3333-8_DMN7022LFGQ-7")
      (fields (field (name "Manufacturer") "TMC(台懋)"))
      (libsource (lib "easyedapro") (part "TMG60N04DF"))
    )
    (comp (ref "Q4")
      (value "TMG60N04DF")
      (footprint "easyedapro:POWERDI3333-8_DMN7022LFGQ-7")
      (fields (field (name "Manufacturer") "TMC(台懋)"))
      (libsource (lib "easyedapro") (part "TMG60N04DF"))
    )
    (comp (ref "Q5")
      (value "TMG60N04DF")
      (footprint "easyedapro:POWERDI3333-8_DMN7022LFGQ-7")
      (fields (field (name "Manufacturer") "TMC(台懋)"))
      (libsource (lib "easyedapro") (part "TMG60N04DF"))
    )
    (comp (ref "Q6")
      (value "TMG60N04DF")
      (footprint "easyedapro:POWERDI3333-8_DMN7022LFGQ-7")
      (fields (field (name "Manufacturer") "TMC(台懋)"))
      (libsource (lib "easyedapro") (part "TMG60N04DF"))
    )
    (comp (ref "R191")
      (value "10Ω")
      (footprint "easyedapro:R0402")
      (description "电阻类型:厚膜电阻;阻值:10Ω;精度:±1%;功率:62.5mW;工作电压:50V;温度系数:±200ppm/℃;")
      (fields
        (field (name "Manufacturer Part") "0402WGF100JTCE")
        (field (name "Manufacturer") "UNI-ROYAL(厚声)")
      )
      (libsource (lib "easyedapro") (part "电阻"))
    )
    (comp (ref "R192")
      (value "10Ω")
      (footprint "easyedapro:R0402")
      (description "电阻类型:厚膜电阻;阻值:10Ω;精度:±1%;功率:62.5mW;工作电压:50V;温度系数:±200ppm/℃;")
      (fields
        (field (name "Manufacturer Part") "0402WGF100JTCE")
        (field (name "Manufacturer") "UNI-ROYAL(厚声)")
      )
      (libsource (lib "easyedapro") (part "电阻"))
    )
    (comp (ref "R193")
      (value "10Ω")
      (footprint "easyedapro:R0402")
      (description "电阻类型:厚膜电阻;阻值:10Ω;精度:±1%;功率:62.5mW;工作电压:50V;温度系数:±200ppm/℃;")
      (fields
        (field (name "Manufacturer Part") "0402WGF100JTCE")
        (field (name "Manufacturer") "UNI-ROYAL(厚声)")
      )
      (libsource (lib "easyedapro") (part "电阻"))
    )
    (comp (ref "R194")
      (value "10Ω")
      (footprint "easyedapro:R0402")
      (description "电阻类型:厚膜电阻;阻值:10Ω;精度:±1%;功率:62.5mW;工作电压:50V;温度系数:±200ppm/℃;")
      (fields
        (field (name "Manufacturer Part") "0402WGF100JTCE")
        (field (name "Manufacturer") "UNI-ROYAL(厚声)")
      )
      (libsource (lib "easyedapro") (part "电阻"))
    )
    (comp (ref "R195")
      (value "10Ω")
      (footprint "easyedapro:R0402")
      (description "电阻类型:厚膜电阻;阻值:10Ω;精度:±1%;功率:62.5mW;工作电压:50V;温度系数:±200ppm/℃;")
      (fields
        (field (name "Manufacturer Part") "0402WGF100JTCE")
        (field (name "Manufacturer") "UNI-ROYAL(厚声)")
      )
      (libsource (lib "easyedapro") (part "电阻"))
    )
    (comp (ref "R196")
      (value "10Ω")
      (footprint "easyedapro:R0402")
      (description "电阻类型:厚膜电阻;阻值:10Ω;精度:±1%;功率:62.5mW;工作电压:50V;温度系数:±200ppm/℃;")
      (fields
        (field (name "Manufacturer Part") "0402WGF100JTCE")
        (field (name "Manufacturer") "UNI-ROYAL(厚声)")
      )
      (libsource (lib "easyedapro") (part "电阻"))
    )
    (comp (ref "R197")
      (value "10Ω")
      (footprint "easyedapro:R0402")
      (description "电阻类型:厚膜电阻;阻值:10Ω;精度:±1%;功率:62.5mW;工作电压:50V;温度系数:±200ppm/℃;")
      (fields
        (field (name "Manufacturer Part") "0402WGF100JTCE")
        (field (name "Manufacturer") "UNI-ROYAL(厚声)")
      )
      (libsource (lib "easyedapro") (part "电阻"))
    )
    (comp (ref "R198")
      (value "10Ω")
      (footprint "easyedapro:R0402")
      (description "电阻类型:厚膜电阻;阻值:10Ω;精度:±1%;功率:62.5mW;工作电压:50V;温度系数:±200ppm/℃;")
      (fields
        (field (name "Manufacturer Part") "0402WGF100JTCE")
        (field (name "Manufacturer") "UNI-ROYAL(厚声)")
      )
      (libsource (lib "easyedapro") (part "电阻"))
    )
    (comp (ref "R199")
      (value "10Ω")
      (footprint "easyedapro:R0402")
      (description "电阻类型:厚膜电阻;阻值:10Ω;精度:±1%;功率:62.5mW;工作电压:50V;温度系数:±200ppm/℃;")
      (fields
        (field (name "Manufacturer Part") "0402WGF100JTCE")
        (field (name "Manufacturer") "UNI-ROYAL(厚声)")
      )
      (libsource (lib "easyedapro") (part "电阻"))
    )
    (comp (ref "R200")
      (value "10Ω")
      (footprint "easyedapro:R0402")
      (description "电阻类型:厚膜电阻;阻值:10Ω;精度:±1%;功率:62.5mW;工作电压:50V;温度系数:±200ppm/℃;")
      (fields
        (field (name "Manufacturer Part") "0402WGF100JTCE")
        (field (name "Manufacturer") "UNI-ROYAL(厚声)")
      )
      (libsource (lib "easyedapro") (part "电阻"))
    )
    (comp (ref "R201")
      (value "10Ω")
      (footprint "easyedapro:R0402")
      (description "电阻类型:厚膜电阻;阻值:10Ω;精度:±1%;功率:62.5mW;工作电压:50V;温度系数:±200ppm/℃;")
      (fields
        (field (name "Manufacturer Part") "0402WGF100JTCE")
        (field (name "Manufacturer") "UNI-ROYAL(厚声)")
      )
      (libsource (lib "easyedapro") (part "电阻"))
    )
    (comp (ref "R202")
      (value "10Ω")
      (footprint "easyedapro:R0402")
      (description "电阻类型:厚膜电阻;阻值:10Ω;精度:±1%;功率:62.5mW;工作电压:50V;温度系数:±200ppm/℃;")
      (fields
        (field (name "Manufacturer Part") "0402WGF100JTCE")
        (field (name "Manufacturer") "UNI-ROYAL(厚声)")
      )
      (libsource (lib "easyedapro") (part "电阻"))
    )
    (comp (ref "R206")
      (value "NCP15XH103F03RC")
      (footprint "easyedapro:R0402")
      (description "阻值:10kΩ;B值(25°C/50°C):3380K;电阻精度:±1%;功率:100mW;B值精度:±1%;最大稳态电流(25°C):310uA;")
      (fields (field (name "Manufacturer") "muRata(村田)"))
      (libsource (lib "easyedapro") (part "NCP15XH103F03RC"))
    )
    (comp (ref "R207")
      (value "3kΩ")
      (footprint "easyedapro:R0402")
      (fields
        (field (name "Manufacturer Part") "0402WGF3001TCE")
        (field (name "Manufacturer") "UNI-ROYAL(厚声)")
      )
      (libsource (lib "easyedapro") (part "电阻"))
    )
    (comp (ref "R239")
      (value "200kΩ")
      (footprint "easyedapro:R0402")
      (fields
        (field (name "Manufacturer Part") "0402WGF2003TCE")
        (field (name "Manufacturer") "UNI-ROYAL(厚声)")
      )
      (libsource (lib "easyedapro") (part "电阻"))
    )
    (comp (ref "R240")
      (value "200kΩ")
      (footprint "easyedapro:R0402")
      (fields
        (field (name "Manufacturer Part") "0402WGF2003TCE")
        (field (name "Manufacturer") "UNI-ROYAL(厚声)")
      )
      (libsource (lib "easyedapro") (part "电阻"))
    )
    (comp (ref "R241")
      (value "200kΩ")
      (footprint "easyedapro:R0402")
      (fields
        (field (name "Manufacturer Part") "0402WGF2003TCE")
        (field (name "Manufacturer") "UNI-ROYAL(厚声)")
      )
      (libsource (lib "easyedapro") (part "电阻"))
    )
    (comp (ref "U")
      (value "~")
      (footprint "easyedapro:PAD_35A")
      (description "焊盘")
      (libsource (lib "easyedapro") (part "PAD_35A"))
    )
    (comp (ref "U40")
      (value "JSM6288Q")
      (footprint "easyedapro:VQFN-24_L4.0-W4.0-P0.50-TL-EP2.7")
      (description "驱动配置:-;负载类型:MOSFET;驱动通道数:-;灌电流(IOL):1.8A;拉电流(IOH):1.5A;工作电压:8V~20V;上升时间(tr):-;下降时间(tf):30ns;")
      (fields (field (name "Manufacturer") "JSMSEMI(杰盛微)"))
      (libsource (lib "easyedapro") (part "JSM6288Q"))
    )
    (comp (ref "V")
      (value "~")
      (footprint "easyedapro:PAD_35A")
      (description "焊盘")
      (libsource (lib "easyedapro") (part "PAD_35A"))
    )
    (comp (ref "W")
      (value "~")
      (footprint "easyedapro:PAD_35A")
      (description "焊盘")
      (libsource (lib "easyedapro") (part "PAD_35A"))
    )
    (comp (ref "C231")
      (value "100pF")
      (footprint "easyedapro:C0402")
      (fields (field (name "Manufacturer Part") "0402CG101J500NT") (field (name "Manufacturer") "FH(风华)"))
      (libsource (lib "easyedapro") (part "CapAcitance"))
    )
    (comp (ref "R211")
      (value "51kΩ")
      (footprint "easyedapro:R0402")
      (fields
        (field (name "Manufacturer Part") "0402WGF5102TCE")
        (field (name "Manufacturer") "UNI-ROYAL(厚声)")
      )
      (libsource (lib "easyedapro") (part "电阻"))
    )
    (comp (ref "R213")
      (value "3kΩ")
      (footprint "easyedapro:R0402")
      (fields (field (name "Manufacturer Part") "FRC0402F3001TS") (field (name "Manufacturer") "FOJAN(富捷)"))
      (libsource (lib "easyedapro") (part "电阻"))
    )
    (comp (ref "R214")
      (value "43kΩ")
      (footprint "easyedapro:R0402")
      (fields
        (field (name "Manufacturer Part") "0402WGF4302TCE")
        (field (name "Manufacturer") "UNI-ROYAL(厚声)")
      )
      (libsource (lib "easyedapro") (part "电阻"))
    )
    (comp (ref "R215")
      (value "51kΩ")
      (footprint "easyedapro:R0402")
      (fields
        (field (name "Manufacturer Part") "0402WGF5102TCE")
        (field (name "Manufacturer") "UNI-ROYAL(厚声)")
      )
      (libsource (lib "easyedapro") (part "电阻"))
    )
    (comp (ref "R216")
      (value "43kΩ")
      (footprint "easyedapro:R0402")
      (fields
        (field (name "Manufacturer Part") "0402WGF4302TCE")
        (field (name "Manufacturer") "UNI-ROYAL(厚声)")
      )
      (libsource (lib "easyedapro") (part "电阻"))
    )
    (comp (ref "R217")
      (value "3kΩ")
      (footprint "easyedapro:R0402")
      (fields (field (name "Manufacturer Part") "FRC0402F3001TS") (field (name "Manufacturer") "FOJAN(富捷)"))
      (libsource (lib "easyedapro") (part "电阻"))
    )
    (comp (ref "R218")
      (value "51kΩ")
      (footprint "easyedapro:R0402")
      (fields
        (field (name "Manufacturer Part") "0402WGF5102TCE")
        (field (name "Manufacturer") "UNI-ROYAL(厚声)")
      )
      (libsource (lib "easyedapro") (part "电阻"))
    )
    (comp (ref "R219")
      (value "43kΩ")
      (footprint "easyedapro:R0402")
      (fields
        (field (name "Manufacturer Part") "0402WGF4302TCE")
        (field (name "Manufacturer") "UNI-ROYAL(厚声)")
      )
      (libsource (lib "easyedapro") (part "电阻"))
    )
    (comp (ref "R220")
      (value "3kΩ")
      (footprint "easyedapro:R0402")
      (fields (field (name "Manufacturer Part") "FRC0402F3001TS") (field (name "Manufacturer") "FOJAN(富捷)"))
      (libsource (lib "easyedapro") (part "电阻"))
    )
    (comp (ref "R225")
      (value "1.2kΩ")
      (footprint "easyedapro:R0402")
      (description "电阻类型:薄膜电阻;阻值:1.2kΩ;精度:±0.1%;功率:63mW;工作电压:50V;温度系数:±25ppm/°C;")
      (fields (field (name "Manufacturer Part") "RT0402BRD071K2L") (field (name "Manufacturer") "YAGEO(国巨)"))
      (libsource (lib "easyedapro") (part "RT0402BRD071K2L"))
    )
    (comp (ref "R226")
      (value "1.2kΩ")
      (footprint "easyedapro:R0402")
      (description "电阻类型:薄膜电阻;阻值:1.2kΩ;精度:±0.1%;功率:63mW;工作电压:50V;温度系数:±25ppm/°C;")
      (fields (field (name "Manufacturer Part") "RT0402BRD071K2L") (field (name "Manufacturer") "YAGEO(国巨)"))
      (libsource (lib "easyedapro") (part "RT0402BRD071K2L"))
    )
    (comp (ref "R227")
      (value "1.2kΩ")
      (footprint "easyedapro:R0402")
      (description "电阻类型:薄膜电阻;阻值:1.2kΩ;精度:±0.1%;功率:63mW;工作电压:50V;温度系数:±25ppm/°C;")
      (fields (field (name "Manufacturer Part") "RT0402BRD071K2L") (field (name "Manufacturer") "YAGEO(国巨)"))
      (libsource (lib "easyedapro") (part "RT0402BRD071K2L"))
    )
    (comp (ref "R228")
      (value "1.2kΩ")
      (footprint "easyedapro:R0402")
      (description "电阻类型:薄膜电阻;阻值:1.2kΩ;精度:±0.1%;功率:63mW;工作电压:50V;温度系数:±25ppm/°C;")
      (fields (field (name "Manufacturer Part") "RT0402BRD071K2L") (field (name "Manufacturer") "YAGEO(国巨)"))
      (libsource (lib "easyedapro") (part "RT0402BRD071K2L"))
    )
    (comp (ref "R229")
      (value "66.5kΩ")
      (footprint "easyedapro:R0402")
      (description "电阻类型:薄膜电阻;阻值:66.5kΩ;精度:±0.1%;功率:62.5mW;工作电压:50V;温度系数:±25ppm/°C;")
      (fields (field (name "Manufacturer Part") "RT0402BRD0766K5L") (field (name "Manufacturer") "YAGEO(国巨)"))
      (libsource (lib "easyedapro") (part "RT0402BRD0766K5L"))
    )
    (comp (ref "R237")
      (value "133kΩ")
      (footprint "easyedapro:R0402")
      (description "电阻类型:薄膜电阻;阻值:133kΩ;精度:±0.1%;功率:63mW;温度系数:±25ppm/°C;")
      (fields (field (name "Manufacturer Part") "RT0402BRD07133KL") (field (name "Manufacturer") "YAGEO(国巨)"))
      (libsource (lib "easyedapro") (part "RT0402BRD07133KL"))
    )
    (comp (ref "R238")
      (value "133kΩ")
      (footprint "easyedapro:R0402")
      (description "电阻类型:薄膜电阻;阻值:133kΩ;精度:±0.1%;功率:63mW;温度系数:±25ppm/°C;")
      (fields (field (name "Manufacturer Part") "RT0402BRD07133KL") (field (name "Manufacturer") "YAGEO(国巨)"))
      (libsource (lib "easyedapro") (part "RT0402BRD07133KL"))
    )
  )
  (nets
    (net (code "1") (name "BOOT0") (class "Default")
      (node (ref "R188") (pin "1") (pinfunction "1_1") (pintype "input"))
      (node (ref "U34") (pin "31") (pinfunction "PF11/BOOT0_31") (pintype "unspecified"))
    )
    (net (code "2") (name "COM_NUTRAL") (class "Default")
      (node (ref "R211") (pin "1") (pinfunction "1_1") (pintype "input"))
      (node (ref "R215") (pin "1") (pinfunction "1_1") (pintype "input"))
      (node (ref "R218") (pin "1") (pinfunction "1_1") (pintype "input"))
      (node (ref "R224") (pin "1") (pinfunction "1_1") (pintype "input"))
    )
    (net (code "3") (name "EMF1") (class "Default")
      (node (ref "R211") (pin "2") (pinfunction "2_2") (pintype "input"))
      (node (ref "R213") (pin "1") (pinfunction "1_1") (pintype "input"))
      (node (ref "R214") (pin "1") (pinfunction "1_1") (pintype "input"))
      (node (ref "R221") (pin "1") (pinfunction "1_1") (pintype "input"))
    )
    (net (code "4") (name "EMF2") (class "Default")
      (node (ref "R215") (pin "2") (pinfunction "2_2") (pintype "input"))
      (node (ref "R216") (pin "1") (pinfunction "1_1") (pintype "input"))
      (node (ref "R217") (pin "1") (pinfunction "1_1") (pintype "input"))
      (node (ref "R222") (pin "1") (pinfunction "1_1") (pintype "input"))
    )
    (net (code "5") (name "EMF3") (class "Default")
      (node (ref "R218") (pin "2") (pinfunction "2_2") (pintype "input"))
      (node (ref "R219") (pin "1") (pinfunction "1_1") (pintype "input"))
      (node (ref "R220") (pin "1") (pinfunction "1_1") (pintype "input"))
      (node (ref "R223") (pin "1") (pinfunction "1_1") (pintype "input"))
    )
    (net (code "6") (name "EMF_NUTRAL") (class "Default")
      (node (ref "C230") (pin "2") (pinfunction "2_2") (pintype "input"))
      (node (ref "R224") (pin "2") (pinfunction "2_2") (pintype "input"))
      (node (ref "U34") (pin "13") (pinfunction "PA7_13") (pintype "unspecified"))
    )
    (net (code "7") (name "EMF_U") (class "Default")
      (node (ref "C227") (pin "2") (pinfunction "2_2") (pintype "input"))
      (node (ref "R221") (pin "2") (pinfunction "2_2") (pintype "input"))
      (node (ref "U34") (pin "10") (pinfunction "PA4_10") (pintype "unspecified"))
    )
    (net (code "8") (name "EMF_V") (class "Default")
      (node (ref "C228") (pin "2") (pinfunction "2_2") (pintype "input"))
      (node (ref "R222") (pin "2") (pinfunction "2_2") (pintype "input"))
      (node (ref "U34") (pin "11") (pinfunction "PA5_11") (pintype "unspecified"))
    )
    (net (code "9") (name "EMF_W") (class "Default")
      (node (ref "C229") (pin "2") (pinfunction "2_2") (pintype "input"))
      (node (ref "R223") (pin "2") (pinfunction "2_2") (pintype "input"))
      (node (ref "U34") (pin "12") (pinfunction "PA6_12") (pintype "unspecified"))
    )
    (net (code "10") (name "FB") (class "Default")
      (node (ref "C233") (pin "2") (pinfunction "2_2") (pintype "input"))
      (node (ref "R186") (pin "2") (pinfunction "2_2") (pintype "input"))
      (node (ref "R242") (pin "1") (pinfunction "1_1") (pintype "input"))
      (node (ref "U39") (pin "3") (pinfunction "FB_3") (pintype "unspecified"))
    )
    (net (code "11") (name "GND") (class "Default")
      (node (ref "ATLINK") (pin "3") (pinfunction "3_3") (pintype "unspecified"))
      (node (ref "C131") (pin "1") (pinfunction "1_1") (pintype "input"))
      (node (ref "C211") (pin "1") (pinfunction "1_1") (pintype "input"))
      (node (ref "C212") (pin "2") (pinfunction "2_2") (pintype "input"))
      (node (ref "C213") (pin "1") (pinfunction "1_1") (pintype "input"))
      (node (ref "C225") (pin "1") (pinfunction "1_1") (pintype "input"))
      (node (ref "C226") (pin "1") (pinfunction "1_1") (pintype "input"))
      (node (ref "C227") (pin "1") (pinfunction "1_1") (pintype "input"))
      (node (ref "C228") (pin "1") (pinfunction "1_1") (pintype "input"))
      (node (ref "C229") (pin "1") (pinfunction "1_1") (pintype "input"))
      (node (ref "C230") (pin "1") (pinfunction "1_1") (pintype "input"))
      (node (ref "C234") (pin "1") (pinfunction "1_1") (pintype "unspecified"))
      (node (ref "C235") (pin "1") (pinfunction "1_1") (pintype "unspecified"))
      (node (ref "C236") (pin "1") (pinfunction "1_1") (pintype "unspecified"))
      (node (ref "C237") (pin "2") (pinfunction "2_2") (pintype "input"))
      (node (ref "DSHOT") (pin "2") (pinfunction "2_2") (pintype "input"))
      (node (ref "L12") (pin "4") (pinfunction "4_4") (pintype "unspecified"))
      (node (ref "LDO1") (pin "2") (pinfunction "VSS_2") (pintype "unspecified"))
      (node (ref "R188") (pin "2") (pinfunction "2_2") (pintype "input"))
      (node (ref "R213") (pin "2") (pinfunction "2_2") (pintype "input"))
      (node (ref "R217") (pin "2") (pinfunction "2_2") (pintype "input"))
      (node (ref "R220") (pin "2") (pinfunction "2_2") (pintype "input"))
      (node (ref "R238") (pin "1") (pinfunction "1_1") (pintype "unspecified"))
      (node (ref "U34") (pin "33") (pinfunction "EP_33") (pintype "unspecified"))
      (node (ref "UART") (pin "3") (pinfunction "3_3") (pintype "unspecified"))
      (node (ref "X3") (pin "2") (pinfunction "GND_2") (pintype "unspecified"))
      (node (ref "X3") (pin "4") (pinfunction "GND_4") (pintype "unspecified"))
    )
    (net (code "12") (name "GNDP") (class "Default")
      (node (ref "C214") (pin "2") (pinfunction "2_2") (pintype "unspecified"))
      (node (ref "C221") (pin "1") (pinfunction "1_1") (pintype "unspecified"))
      (node (ref "C238") (pin "2") (pinfunction "2_2") (pintype "unspecified"))
      (node (ref "C239") (pin "2") (pinfunction "2_2") (pintype "unspecified"))
      (node (ref "C240") (pin "2") (pinfunction "2_2") (pintype "unspecified"))
      (node (ref "C241") (pin "2") (pinfunction "2_2") (pintype "input"))
      (node (ref "C249") (pin "1") (pinfunction "1_1") (pintype "unspecified"))
      (node (ref "C250") (pin "1") (pinfunction "1_1") (pintype "unspecified"))
      (node (ref "C251") (pin "1") (pinfunction "1_1") (pintype "unspecified"))
      (node (ref "C252") (pin "1") (pinfunction "1_1") (pintype "unspecified"))
      (node (ref "Q2") (pin "1") (pinfunction "S_1") (pintype "unspecified"))
      (node (ref "Q2") (pin "2") (pinfunction "S_2") (pintype "unspecified"))
      (node (ref "Q2") (pin "3") (pinfunction "S_3") (pintype "unspecified"))
      (node (ref "Q4") (pin "1") (pinfunction "S_1") (pintype "unspecified"))
      (node (ref "Q4") (pin "2") (pinfunction "S_2") (pintype "unspecified"))
      (node (ref "Q4") (pin "3") (pinfunction "S_3") (pintype "unspecified"))
      (node (ref "Q6") (pin "1") (pinfunction "S_1") (pintype "unspecified"))
      (node (ref "Q6") (pin "2") (pinfunction "S_2") (pintype "unspecified"))
      (node (ref "Q6") (pin "3") (pinfunction "S_3") (pintype "unspecified"))
      (node (ref "R203") (pin "1") (pinfunction "1_1") (pintype "unspecified"))
      (node (ref "R204") (pin "2") (pinfunction "2_2") (pintype "input"))
      (node (ref "R206") (pin "1") (pinfunction "1_1") (pintype "input"))
      (node (ref "U40") (pin "25") (pinfunction "EP_25") (pintype "unspecified"))
      (node (ref "U40") (pin "6") (pinfunction "COM_6") (pintype "unspecified"))
      (node (ref "U43") (pin "2") (pinfunction "GND_2") (pintype "unspecified"))
    )
    (net (code "13") (name "GND_IN") (class "Default")
      (node (ref "BUS_OUT") (pin "1") (pinfunction "1_1") (pintype "input"))
      (node (ref "C205") (pin "2") (pinfunction "2_2") (pintype "input"))
      (node (ref "C208") (pin "1") (pinfunction "1_1") (pintype "unspecified"))
      (node (ref "C210") (pin "1") (pinfunction "1_1") (pintype "unspecified"))
      (node (ref "C243") (pin "1") (pinfunction "1_1") (pintype "unspecified"))
      (node (ref "C244") (pin "1") (pinfunction "1_1") (pintype "unspecified"))
      (node (ref "C245") (pin "1") (pinfunction "1_1") (pintype "unspecified"))
      (node (ref "C246") (pin "1") (pinfunction "1_1") (pintype "unspecified"))
      (node (ref "C247") (pin "1") (pinfunction "1_1") (pintype "unspecified"))
      (node (ref "C248") (pin "1") (pinfunction "1_1") (pintype "unspecified"))
      (node (ref "L12") (pin "1") (pinfunction "1_1") (pintype "unspecified"))
      (node (ref "R203") (pin "2") (pinfunction "2_2") (pintype "unspecified"))
      (node (ref "R205") (pin "2") (pinfunction "2_2") (pintype "input"))
      (node (ref "R231") (pin "2") (pinfunction "2_2") (pintype "input"))
      (node (ref "R242") (pin "2") (pinfunction "2_2") (pintype "input"))
      (node (ref "R244") (pin "2") (pinfunction "2_2") (pintype "input"))
      (node (ref "U39") (pin "2") (pinfunction "GND_2") (pintype "unspecified"))
      (node (ref "U41") (pin "2") (pinfunction "A_2") (pintype "unspecified"))
    )
    (net (code "14") (name "HO1") (class "Default")
      (node (ref "D40") (pin "1") (pinfunction "K_1") (pintype "unspecified"))
      (node (ref "R191") (pin "1") (pinfunction "1_1") (pintype "input"))
      (node (ref "U40") (pin "19") (pinfunction "HO1_19") (pintype "unspecified"))
    )
    (net (code "15") (name "HO2") (class "Default")
      (node (ref "D41") (pin "1") (pinfunction "K_1") (pintype "unspecified"))
      (node (ref "R193") (pin "1") (pinfunction "1_1") (pintype "input"))
      (node (ref "U40") (pin "16") (pinfunction "HO2_16") (pintype "unspecified"))
    )
    (net (code "16") (name "HO3") (class "Default")
      (node (ref "D42") (pin "1") (pinfunction "K_1") (pintype "unspecified"))
      (node (ref "R195") (pin "1") (pinfunction "1_1") (pintype "input"))
      (node (ref "U40") (pin "13") (pinfunction "HO3_13") (pintype "unspecified"))
    )
    (net (code "17") (name "I_BUS_GND") (class "Default")
      (node (ref "C220") (pin "2") (pinfunction "2_2") (pintype "input"))
      (node (ref "R205") (pin "1") (pinfunction "1_1") (pintype "input"))
      (node (ref "R226") (pin "1") (pinfunction "1_1") (pintype "unspecified"))
    )
    (net (code "18") (name "I_BUS_SHUNT") (class "Default")
      (node (ref "C220") (pin "1") (pinfunction "1_1") (pintype "input"))
      (node (ref "R204") (pin "1") (pinfunction "1_1") (pintype "input"))
      (node (ref "R225") (pin "1") (pinfunction "1_1") (pintype "unspecified"))
    )
    (net (code "19") (name "LED_G") (class "Default")
      (node (ref "LED1") (pin "1") (pinfunction "R-_1") (pintype "unspecified"))
      (node (ref "U34") (pin "17") (pinfunction "PB10_17") (pintype "unspecified"))
    )
    (net (code "20") (name "LED_R") (class "Default")
      (node (ref "LED1") (pin "3") (pinfunction "UG-_3") (pintype "unspecified"))
      (node (ref "U34") (pin "7") (pinfunction "PA1_7") (pintype "unspecified"))
    )
    (net (code "21") (name "LO1") (class "Default")
      (node (ref "D43") (pin "1") (pinfunction "K_1") (pintype "unspecified"))
      (node (ref "R192") (pin "1") (pinfunction "1_1") (pintype "input"))
      (node (ref "U40") (pin "11") (pinfunction "LO1_11") (pintype "unspecified"))
    )
    (net (code "22") (name "LO2") (class "Default")
      (node (ref "D44") (pin "1") (pinfunction "K_1") (pintype "unspecified"))
      (node (ref "R194") (pin "1") (pinfunction "1_1") (pintype "input"))
      (node (ref "U40") (pin "10") (pinfunction "LO2_10") (pintype "unspecified"))
    )
    (net (code "23") (name "LO3") (class "Default")
      (node (ref "D45") (pin "1") (pinfunction "K_1") (pintype "unspecified"))
      (node (ref "R196") (pin "1") (pinfunction "1_1") (pintype "input"))
      (node (ref "U40") (pin "9") (pinfunction "LO3_9") (pintype "unspecified"))
    )
    (net (code "24") (name "MOS_NTC") (class "Default")
      (node (ref "R206") (pin "2") (pinfunction "2_2") (pintype "input"))
      (node (ref "R207") (pin "1") (pinfunction "1_1") (pintype "input"))
      (node (ref "R209") (pin "1") (pinfunction "1_1") (pintype "input"))
    )
    (net (code "25") (name "MOS_TEMP") (class "Default")
      (node (ref "C226") (pin "2") (pinfunction "2_2") (pintype "input"))
      (node (ref "R209") (pin "2") (pinfunction "2_2") (pintype "input"))
      (node (ref "U34") (pin "5") (pinfunction "PF9_5") (pintype "unspecified"))
    )
    (net (code "26") (name "NRST") (class "Default")
      (node (ref "C211") (pin "2") (pinfunction "2_2") (pintype "input"))
      (node (ref "U34") (pin "4") (pinfunction "NRST/PF2_4") (pintype "unspecified"))
    )
    (net (code "27") (name "Net-(C231-Pad1)") (class "Default")
      (node (ref "C231") (pin "1") (pinfunction "1_1") (pintype "input"))
      (node (ref "R226") (pin "2") (pinfunction "2_2") (pintype "unspecified"))
      (node (ref "R228") (pin "1") (pinfunction "1_1") (pintype "unspecified"))
    )
    (net (code "28") (name "Net-(C231-Pad2)") (class "Default")
      (node (ref "C231") (pin "2") (pinfunction "2_2") (pintype "input"))
      (node (ref "R225") (pin "2") (pinfunction "2_2") (pintype "unspecified"))
      (node (ref "R227") (pin "1") (pinfunction "1_1") (pintype "unspecified"))
    )
    (net (code "29") (name "Net-(D40-A)") (class "Default")
      (node (ref "D40") (pin "2") (pinfunction "A_2") (pintype "unspecified"))
      (node (ref "Q1") (pin "4") (pinfunction "G_4") (pintype "unspecified"))
      (node (ref "R191") (pin "2") (pinfunction "2_2") (pintype "input"))
      (node (ref "R239") (pin "2") (pinfunction "2_2") (pintype "input"))
    )
    (net (code "30") (name "Net-(D41-A)") (class "Default")
      (node (ref "D41") (pin "2") (pinfunction "A_2") (pintype "unspecified"))
      (node (ref "Q3") (pin "4") (pinfunction "G_4") (pintype "unspecified"))
      (node (ref "R193") (pin "2") (pinfunction "2_2") (pintype "input"))
      (node (ref "R240") (pin "2") (pinfunction "2_2") (pintype "input"))
    )
    (net (code "31") (name "Net-(D42-A)") (class "Default")
      (node (ref "D42") (pin "2") (pinfunction "A_2") (pintype "unspecified"))
      (node (ref "Q5") (pin "4") (pinfunction "G_4") (pintype "unspecified"))
      (node (ref "R195") (pin "2") (pinfunction "2_2") (pintype "input"))
      (node (ref "R241") (pin "2") (pinfunction "2_2") (pintype "input"))
    )
    (net (code "32") (name "Net-(D43-A)") (class "Default")
      (node (ref "D43") (pin "2") (pinfunction "A_2") (pintype "unspecified"))
      (node (ref "Q2") (pin "4") (pinfunction "G_4") (pintype "unspecified"))
      (node (ref "R192") (pin "2") (pinfunction "2_2") (pintype "input"))
    )
    (net (code "33") (name "Net-(D44-A)") (class "Default")
      (node (ref "D44") (pin "2") (pinfunction "A_2") (pintype "unspecified"))
      (node (ref "Q4") (pin "4") (pinfunction "G_4") (pintype "unspecified"))
      (node (ref "R194") (pin "2") (pinfunction "2_2") (pintype "input"))
    )
    (net (code "34") (name "Net-(D45-A)") (class "Default")
      (node (ref "D45") (pin "2") (pinfunction "A_2") (pintype "unspecified"))
      (node (ref "Q6") (pin "4") (pinfunction "G_4") (pintype "unspecified"))
      (node (ref "R196") (pin "2") (pinfunction "2_2") (pintype "input"))
    )
    (net (code "35") (name "Net-(LDO1-CE)") (class "Default")
      (node (ref "C234") (pin "2") (pinfunction "2_2") (pintype "unspecified"))
      (node (ref "C235") (pin "2") (pinfunction "2_2") (pintype "unspecified"))
      (node (ref "L12") (pin "3") (pinfunction "3_3") (pintype "unspecified"))
      (node (ref "LDO1") (pin "1") (pinfunction "VIN_1") (pintype "unspecified"))
      (node (ref "LDO1") (pin "3") (pinfunction "CE_3") (pintype "unspecified"))
    )
    (net (code "36") (name "Net-(LED1-+R)") (class "Default")
      (node (ref "LED1") (pin "2") (pinfunction "+R_2") (pintype "unspecified"))
      (node (ref "R190") (pin "2") (pinfunction "2_2") (pintype "input"))
    )
    (net (code "37") (name "Net-(LED1-+UG)") (class "Default")
      (node (ref "LED1") (pin "4") (pinfunction "+UG_4") (pintype "unspecified"))
      (node (ref "R189") (pin "2") (pinfunction "2_2") (pintype "input"))
    )
    (net (code "38") (name "Net-(U34-PA11)") (class "Default")
      (node (ref "PA11") (pin "1") (pinfunction "1_1") (pintype "input"))
      (node (ref "U34") (pin "21") (pinfunction "PA11_21") (pintype "unspecified"))
    )
    (net (code "39") (name "Net-(U34-PA15)") (class "Default")
      (node (ref "PA15") (pin "1") (pinfunction "1_1") (pintype "input"))
      (node (ref "U34") (pin "25") (pinfunction "PA15_25") (pintype "unspecified"))
    )
    (net (code "40") (name "Net-(U34-PB3)") (class "Default")
      (node (ref "PB3") (pin "1") (pinfunction "1_1") (pintype "input"))
      (node (ref "U34") (pin "26") (pinfunction "PB3_26") (pintype "unspecified"))
    )
    (net (code "41") (name "Net-(U34-PB4)") (class "Default")
      (node (ref "PB4") (pin "1") (pinfunction "1_1") (pintype "input"))
      (node (ref "U34") (pin "27") (pinfunction "PB4_27") (pintype "unspecified"))
    )
    (net (code "42") (name "Net-(U34-PB5)") (class "Default")
      (node (ref "PB5") (pin "1") (pinfunction "1_1") (pintype "input"))
      (node (ref "U34") (pin "28") (pinfunction "PB5_28") (pintype "unspecified"))
    )
    (net (code "43") (name "Net-(U39-BST)") (class "Default")
      (node (ref "C232") (pin "2") (pinfunction "2_2") (pintype "input"))
      (node (ref "U39") (pin "1") (pinfunction "BST_1") (pintype "unspecified"))
    )
    (net (code "44") (name "Net-(U39-EN)") (class "Default")
      (node (ref "R243") (pin "2") (pinfunction "2_2") (pintype "input"))
      (node (ref "R244") (pin "1") (pinfunction "1_1") (pintype "input"))
      (node (ref "U39") (pin "4") (pinfunction "EN_4") (pintype "unspecified"))
    )
    (net (code "45") (name "Net-(U39-SW)") (class "Default")
      (node (ref "C232") (pin "1") (pinfunction "1_1") (pintype "input"))
      (node (ref "L11") (pin "1") (pinfunction "1_1") (pintype "unspecified"))
      (node (ref "U39") (pin "6") (pinfunction "SW_6") (pintype "unspecified"))
    )
    (net (code "46") (name "Net-(U40-HIN1)") (class "Default")
      (node (ref "R197") (pin "2") (pinfunction "2_2") (pintype "input"))
      (node (ref "U40") (pin "22") (pinfunction "HIN1_22") (pintype "unspecified"))
    )
    (net (code "47") (name "Net-(U40-HIN2)") (class "Default")
      (node (ref "R199") (pin "2") (pinfunction "2_2") (pintype "input"))
      (node (ref "U40") (pin "23") (pinfunction "HIN2_23") (pintype "unspecified"))
    )
    (net (code "48") (name "Net-(U40-HIN3)") (class "Default")
      (node (ref "R201") (pin "2") (pinfunction "2_2") (pintype "input"))
      (node (ref "U40") (pin "24") (pinfunction "HIN3_24") (pintype "unspecified"))
    )
    (net (code "49") (name "Net-(U40-LIN1)") (class "Default")
      (node (ref "R198") (pin "2") (pinfunction "2_2") (pintype "input"))
      (node (ref "U40") (pin "1") (pinfunction "LIN1_1") (pintype "unspecified"))
    )
    (net (code "50") (name "Net-(U40-LIN2)") (class "Default")
      (node (ref "R200") (pin "2") (pinfunction "2_2") (pintype "input"))
      (node (ref "U40") (pin "2") (pinfunction "LIN2_2") (pintype "unspecified"))
    )
    (net (code "51") (name "Net-(U40-LIN3)") (class "Default")
      (node (ref "R202") (pin "2") (pinfunction "2_2") (pintype "input"))
      (node (ref "U40") (pin "3") (pinfunction "LIN3_3") (pintype "unspecified"))
    )
    (net (code "52") (name "OP3_INM_BUS") (class "Default")
      (node (ref "R228") (pin "2") (pinfunction "2_2") (pintype "unspecified"))
      (node (ref "R229") (pin "1") (pinfunction "1_1") (pintype "unspecified"))
      (node (ref "U34") (pin "16") (pinfunction "PB2_16") (pintype "unspecified"))
    )
    (net (code "53") (name "OP3_INP_BUS") (class "Default")
      (node (ref "R227") (pin "2") (pinfunction "2_2") (pintype "unspecified"))
      (node (ref "R237") (pin "2") (pinfunction "2_2") (pintype "unspecified"))
      (node (ref "R238") (pin "2") (pinfunction "2_2") (pintype "unspecified"))
      (node (ref "U34") (pin "14") (pinfunction "PB0_14") (pintype "unspecified"))
    )
    (net (code "54") (name "OP3_OUT_BUS") (class "Default")
      (node (ref "R229") (pin "2") (pinfunction "2_2") (pintype "unspecified"))
      (node (ref "U34") (pin "15") (pinfunction "PB1_15") (pintype "unspecified"))
    )
    (net (code "55") (name "OSC_IN") (class "Default")
      (node (ref "C212") (pin "1") (pinfunction "1_1") (pintype "input"))
      (node (ref "U34") (pin "2") (pinfunction "PF0_2") (pintype "unspecified"))
      (node (ref "X3") (pin "1") (pinfunction "OSC1_1") (pintype "unspecified"))
    )
    (net (code "56") (name "OSC_OUT") (class "Default")
      (node (ref "C213") (pin "2") (pinfunction "2_2") (pintype "input"))
      (node (ref "U34") (pin "3") (pinfunction "PF1_3") (pintype "unspecified"))
      (node (ref "X3") (pin "3") (pinfunction "OSC2_3") (pintype "unspecified"))
    )
    (net (code "57") (name "OUT1") (class "Default")
      (node (ref "C215") (pin "1") (pinfunction "1_1") (pintype "unspecified"))
      (node (ref "Q1") (pin "1") (pinfunction "S_1") (pintype "unspecified"))
      (node (ref "Q1") (pin "2") (pinfunction "S_2") (pintype "unspecified"))
      (node (ref "Q1") (pin "3") (pinfunction "S_3") (pintype "unspecified"))
      (node (ref "Q2") (pin "5") (pinfunction "D_5") (pintype "unspecified"))
      (node (ref "R214") (pin "2") (pinfunction "2_2") (pintype "input"))
      (node (ref "R239") (pin "1") (pinfunction "1_1") (pintype "input"))
      (node (ref "U") (pin "1") (pinfunction "1_1") (pintype "input"))
      (node (ref "U40") (pin "18") (pinfunction "VS1_18") (pintype "unspecified"))
    )
    (net (code "58") (name "OUT2") (class "Default")
      (node (ref "C217") (pin "1") (pinfunction "1_1") (pintype "unspecified"))
      (node (ref "Q3") (pin "1") (pinfunction "S_1") (pintype "unspecified"))
      (node (ref "Q3") (pin "2") (pinfunction "S_2") (pintype "unspecified"))
      (node (ref "Q3") (pin "3") (pinfunction "S_3") (pintype "unspecified"))
      (node (ref "Q4") (pin "5") (pinfunction "D_5") (pintype "unspecified"))
      (node (ref "R216") (pin "2") (pinfunction "2_2") (pintype "input"))
      (node (ref "R240") (pin "1") (pinfunction "1_1") (pintype "input"))
      (node (ref "U40") (pin "15") (pinfunction "VS2_15") (pintype "unspecified"))
      (node (ref "V") (pin "1") (pinfunction "1_1") (pintype "input"))
    )
    (net (code "59") (name "OUT3") (class "Default")
      (node (ref "C219") (pin "1") (pinfunction "1_1") (pintype "unspecified"))
      (node (ref "Q5") (pin "1") (pinfunction "S_1") (pintype "unspecified"))
      (node (ref "Q5") (pin "2") (pinfunction "S_2") (pintype "unspecified"))
      (node (ref "Q5") (pin "3") (pinfunction "S_3") (pintype "unspecified"))
      (node (ref "Q6") (pin "5") (pinfunction "D_5") (pintype "unspecified"))
      (node (ref "R219") (pin "2") (pinfunction "2_2") (pintype "input"))
      (node (ref "R241") (pin "1") (pinfunction "1_1") (pintype "input"))
      (node (ref "U40") (pin "12") (pinfunction "VS3_12") (pintype "unspecified"))
      (node (ref "W") (pin "1") (pinfunction "1_1") (pintype "input"))
    )
    (net (code "60") (name "PWM_IN_DSHOT") (class "Default")
      (node (ref "DSHOT") (pin "1") (pinfunction "1_1") (pintype "input"))
      (node (ref "U34") (pin "32") (pinfunction "PB8_32") (pintype "unspecified"))
    )
    (net (code "61") (name "SWCLK") (class "Default")
      (node (ref "ATLINK") (pin "2") (pinfunction "2_2") (pintype "unspecified"))
      (node (ref "U34") (pin "24") (pinfunction "PA14_24") (pintype "unspecified"))
    )
    (net (code "62") (name "SWDIO") (class "Default")
      (node (ref "ATLINK") (pin "1") (pinfunction "1_1") (pintype "unspecified"))
      (node (ref "U34") (pin "23") (pinfunction "PA13_23") (pintype "unspecified"))
    )
    (net (code "63") (name "TIM1_CH1") (class "Default")
      (node (ref "R197") (pin "1") (pinfunction "1_1") (pintype "input"))
      (node (ref "U34") (pin "18") (pinfunction "PA8_18") (pintype "unspecified"))
    )
    (net (code "64") (name "TIM1_CH1N") (class "Default")
      (node (ref "R198") (pin "1") (pinfunction "1_1") (pintype "input"))
      (node (ref "U34") (pin "30") (pinfunction "PB7_30") (pintype "unspecified"))
    )
    (net (code "65") (name "TIM1_CH2") (class "Default")
      (node (ref "R199") (pin "1") (pinfunction "1_1") (pintype "input"))
      (node (ref "U34") (pin "19") (pinfunction "PA9_19") (pintype "unspecified"))
    )
    (net (code "66") (name "TIM1_CH2N") (class "Default")
      (node (ref "R200") (pin "1") (pinfunction "1_1") (pintype "input"))
      (node (ref "U34") (pin "22") (pinfunction "PA12_22") (pintype "unspecified"))
    )
    (net (code "67") (name "TIM1_CH3") (class "Default")
      (node (ref "R201") (pin "1") (pinfunction "1_1") (pintype "input"))
      (node (ref "U34") (pin "20") (pinfunction "PA10_20") (pintype "unspecified"))
    )
    (net (code "68") (name "TIM1_CH3N") (class "Default")
      (node (ref "R202") (pin "1") (pinfunction "1_1") (pintype "input"))
      (node (ref "U34") (pin "29") (pinfunction "PB6_29") (pintype "unspecified"))
    )
    (net (code "69") (name "UART_RX") (class "Default")
      (node (ref "U34") (pin "9") (pinfunction "PA3_9") (pintype "unspecified"))
      (node (ref "UART") (pin "2") (pinfunction "2_2") (pintype "unspecified"))
    )
    (net (code "70") (name "UART_TX") (class "Default")
      (node (ref "U34") (pin "8") (pinfunction "PA2_8") (pintype "unspecified"))
      (node (ref "UART") (pin "1") (pinfunction "1_1") (pintype "unspecified"))
    )
    (net (code "71") (name "VB1") (class "Default")
      (node (ref "C215") (pin "2") (pinfunction "2_2") (pintype "unspecified"))
      (node (ref "D37") (pin "1") (pinfunction "K_1") (pintype "unspecified"))
      (node (ref "U40") (pin "20") (pinfunction "VB1_20") (pintype "unspecified"))
    )
    (net (code "72") (name "VB2") (class "Default")
      (node (ref "C217") (pin "2") (pinfunction "2_2") (pintype "unspecified"))
      (node (ref "D38") (pin "1") (pinfunction "K_1") (pintype "unspecified"))
      (node (ref "U40") (pin "17") (pinfunction "VB2_17") (pintype "unspecified"))
    )
    (net (code "73") (name "VB3") (class "Default")
      (node (ref "C219") (pin "2") (pinfunction "2_2") (pintype "unspecified"))
      (node (ref "D39") (pin "1") (pinfunction "K_1") (pintype "unspecified"))
      (node (ref "U40") (pin "14") (pinfunction "VB3_14") (pintype "unspecified"))
    )
    (net (code "74") (name "VBOOST") (class "Default")
      (node (ref "C214") (pin "1") (pinfunction "1_1") (pintype "unspecified"))
      (node (ref "D37") (pin "2") (pinfunction "A_2") (pintype "unspecified"))
      (node (ref "D38") (pin "2") (pinfunction "A_2") (pintype "unspecified"))
      (node (ref "D39") (pin "2") (pinfunction "A_2") (pintype "unspecified"))
      (node (ref "L14") (pin "2") (pinfunction "2_2") (pintype "unspecified"))
      (node (ref "L15") (pin "2") (pinfunction "2_2") (pintype "unspecified"))
      (node (ref "U40") (pin "4") (pinfunction "VCC_4") (pintype "unspecified"))
    )
    (net (code "75") (name "VBUS") (class "Default")
      (node (ref "BUS_IN") (pin "1") (pinfunction "1_1") (pintype "input"))
      (node (ref "C205") (pin "1") (pinfunction "1_1") (pintype "input"))
      (node (ref "C208") (pin "2") (pinfunction "2_2") (pintype "unspecified"))
      (node (ref "C221") (pin "2") (pinfunction "2_2") (pintype "unspecified"))
      (node (ref "C238") (pin "1") (pinfunction "1_1") (pintype "unspecified"))
      (node (ref "C239") (pin "1") (pinfunction "1_1") (pintype "unspecified"))
      (node (ref "C240") (pin "1") (pinfunction "1_1") (pintype "unspecified"))
      (node (ref "C245") (pin "2") (pinfunction "2_2") (pintype "unspecified"))
      (node (ref "C246") (pin "2") (pinfunction "2_2") (pintype "unspecified"))
      (node (ref "C247") (pin "2") (pinfunction "2_2") (pintype "unspecified"))
      (node (ref "C248") (pin "2") (pinfunction "2_2") (pintype "unspecified"))
      (node (ref "C249") (pin "2") (pinfunction "2_2") (pintype "unspecified"))
      (node (ref "C250") (pin "2") (pinfunction "2_2") (pintype "unspecified"))
      (node (ref "C251") (pin "2") (pinfunction "2_2") (pintype "unspecified"))
      (node (ref "C252") (pin "2") (pinfunction "2_2") (pintype "unspecified"))
      (node (ref "L15") (pin "1") (pinfunction "1_1") (pintype "unspecified"))
      (node (ref "Q1") (pin "5") (pinfunction "D_5") (pintype "unspecified"))
      (node (ref "Q3") (pin "5") (pinfunction "D_5") (pintype "unspecified"))
      (node (ref "Q5") (pin "5") (pinfunction "D_5") (pintype "unspecified"))
      (node (ref "R230") (pin "1") (pinfunction "1_1") (pintype "input"))
      (node (ref "R243") (pin "1") (pinfunction "1_1") (pintype "input"))
      (node (ref "U39") (pin "5") (pinfunction "VIN_5") (pintype "unspecified"))
      (node (ref "U41") (pin "1") (pinfunction "C_1") (pintype "unspecified"))
      (node (ref "U43") (pin "3") (pinfunction "Vin_3") (pintype "unspecified"))
    )
    (net (code "76") (name "VBUS_REF") (class "Default")
      (node (ref "R208") (pin "1") (pinfunction "1_1") (pintype "input"))
      (node (ref "R230") (pin "2") (pinfunction "2_2") (pintype "input"))
      (node (ref "R231") (pin "1") (pinfunction "1_1") (pintype "input"))
    )
    (net (code "77") (name "VCC_3V3") (class "Default")
      (node (ref "C236") (pin "2") (pinfunction "2_2") (pintype "unspecified"))
      (node (ref "L13") (pin "1") (pinfunction "1_1") (pintype "unspecified"))
      (node (ref "LDO1") (pin "5") (pinfunction "VOUT_5") (pintype "unspecified"))
    )
    (net (code "78") (name "VCC_5V") (class "Default")
      (node (ref "C210") (pin "2") (pinfunction "2_2") (pintype "unspecified"))
      (node (ref "C233") (pin "1") (pinfunction "1_1") (pintype "input"))
      (node (ref "C243") (pin "2") (pinfunction "2_2") (pintype "unspecified"))
      (node (ref "C244") (pin "2") (pinfunction "2_2") (pintype "unspecified"))
      (node (ref "L11") (pin "2") (pinfunction "2_2") (pintype "unspecified"))
      (node (ref "L12") (pin "2") (pinfunction "2_2") (pintype "unspecified"))
      (node (ref "R186") (pin "1") (pinfunction "1_1") (pintype "input"))
    )
    (net (code "79") (name "VCC_12V") (class "Default")
      (node (ref "C241") (pin "1") (pinfunction "1_1") (pintype "input"))
      (node (ref "L14") (pin "1") (pinfunction "1_1") (pintype "unspecified"))
      (node (ref "U43") (pin "1") (pinfunction "Vout_1") (pintype "unspecified"))
    )
    (net (code "80") (name "VDD_3V3") (class "Default")
      (node (ref "C131") (pin "2") (pinfunction "2_2") (pintype "input"))
      (node (ref "C237") (pin "1") (pinfunction "1_1") (pintype "input"))
      (node (ref "L13") (pin "2") (pinfunction "2_2") (pintype "unspecified"))
      (node (ref "R189") (pin "1") (pinfunction "1_1") (pintype "input"))
      (node (ref "R190") (pin "1") (pinfunction "1_1") (pintype "input"))
      (node (ref "R207") (pin "2") (pinfunction "2_2") (pintype "input"))
      (node (ref "R237") (pin "1") (pinfunction "1_1") (pintype "unspecified"))
      (node (ref "U34") (pin "1") (pinfunction "VDD/VDDA_1") (pintype "unspecified"))
    )
    (net (code "81") (name "V_BUS_FB") (class "Default")
      (node (ref "C225") (pin "2") (pinfunction "2_2") (pintype "input"))
      (node (ref "R208") (pin "2") (pinfunction "2_2") (pintype "input"))
      (node (ref "U34") (pin "6") (pinfunction "PA0_6") (pintype "unspecified"))
    )
    (net (code "82") (name "unconnected-(LDO1-NC-Pad4)") (class "Default")
      (node (ref "LDO1") (pin "4") (pinfunction "NC_4") (pintype "unspecified+no_connect"))
    )
    (net (code "83") (name "unconnected-(U40-NC-Pad5)") (class "Default")
      (node (ref "U40") (pin "5") (pinfunction "NC_5") (pintype "unspecified+no_connect"))
    )
    (net (code "84") (name "unconnected-(U40-NC-Pad7)") (class "Default")
      (node (ref "U40") (pin "7") (pinfunction "NC_7") (pintype "unspecified+no_connect"))
    )
    (net (code "85") (name "unconnected-(U40-NC-Pad8)") (class "Default")
      (node (ref "U40") (pin "8") (pinfunction "NC_8") (pintype "unspecified+no_connect"))
    )
    (net (code "86") (name "unconnected-(U40-NC-Pad21)") (class "Default")
      (node (ref "U40") (pin "21") (pinfunction "NC_21") (pintype "unspecified+no_connect"))
    )
  )
)
